# keyboard_main.net
KiCad netlist of a schematic drawn in Altium Designer
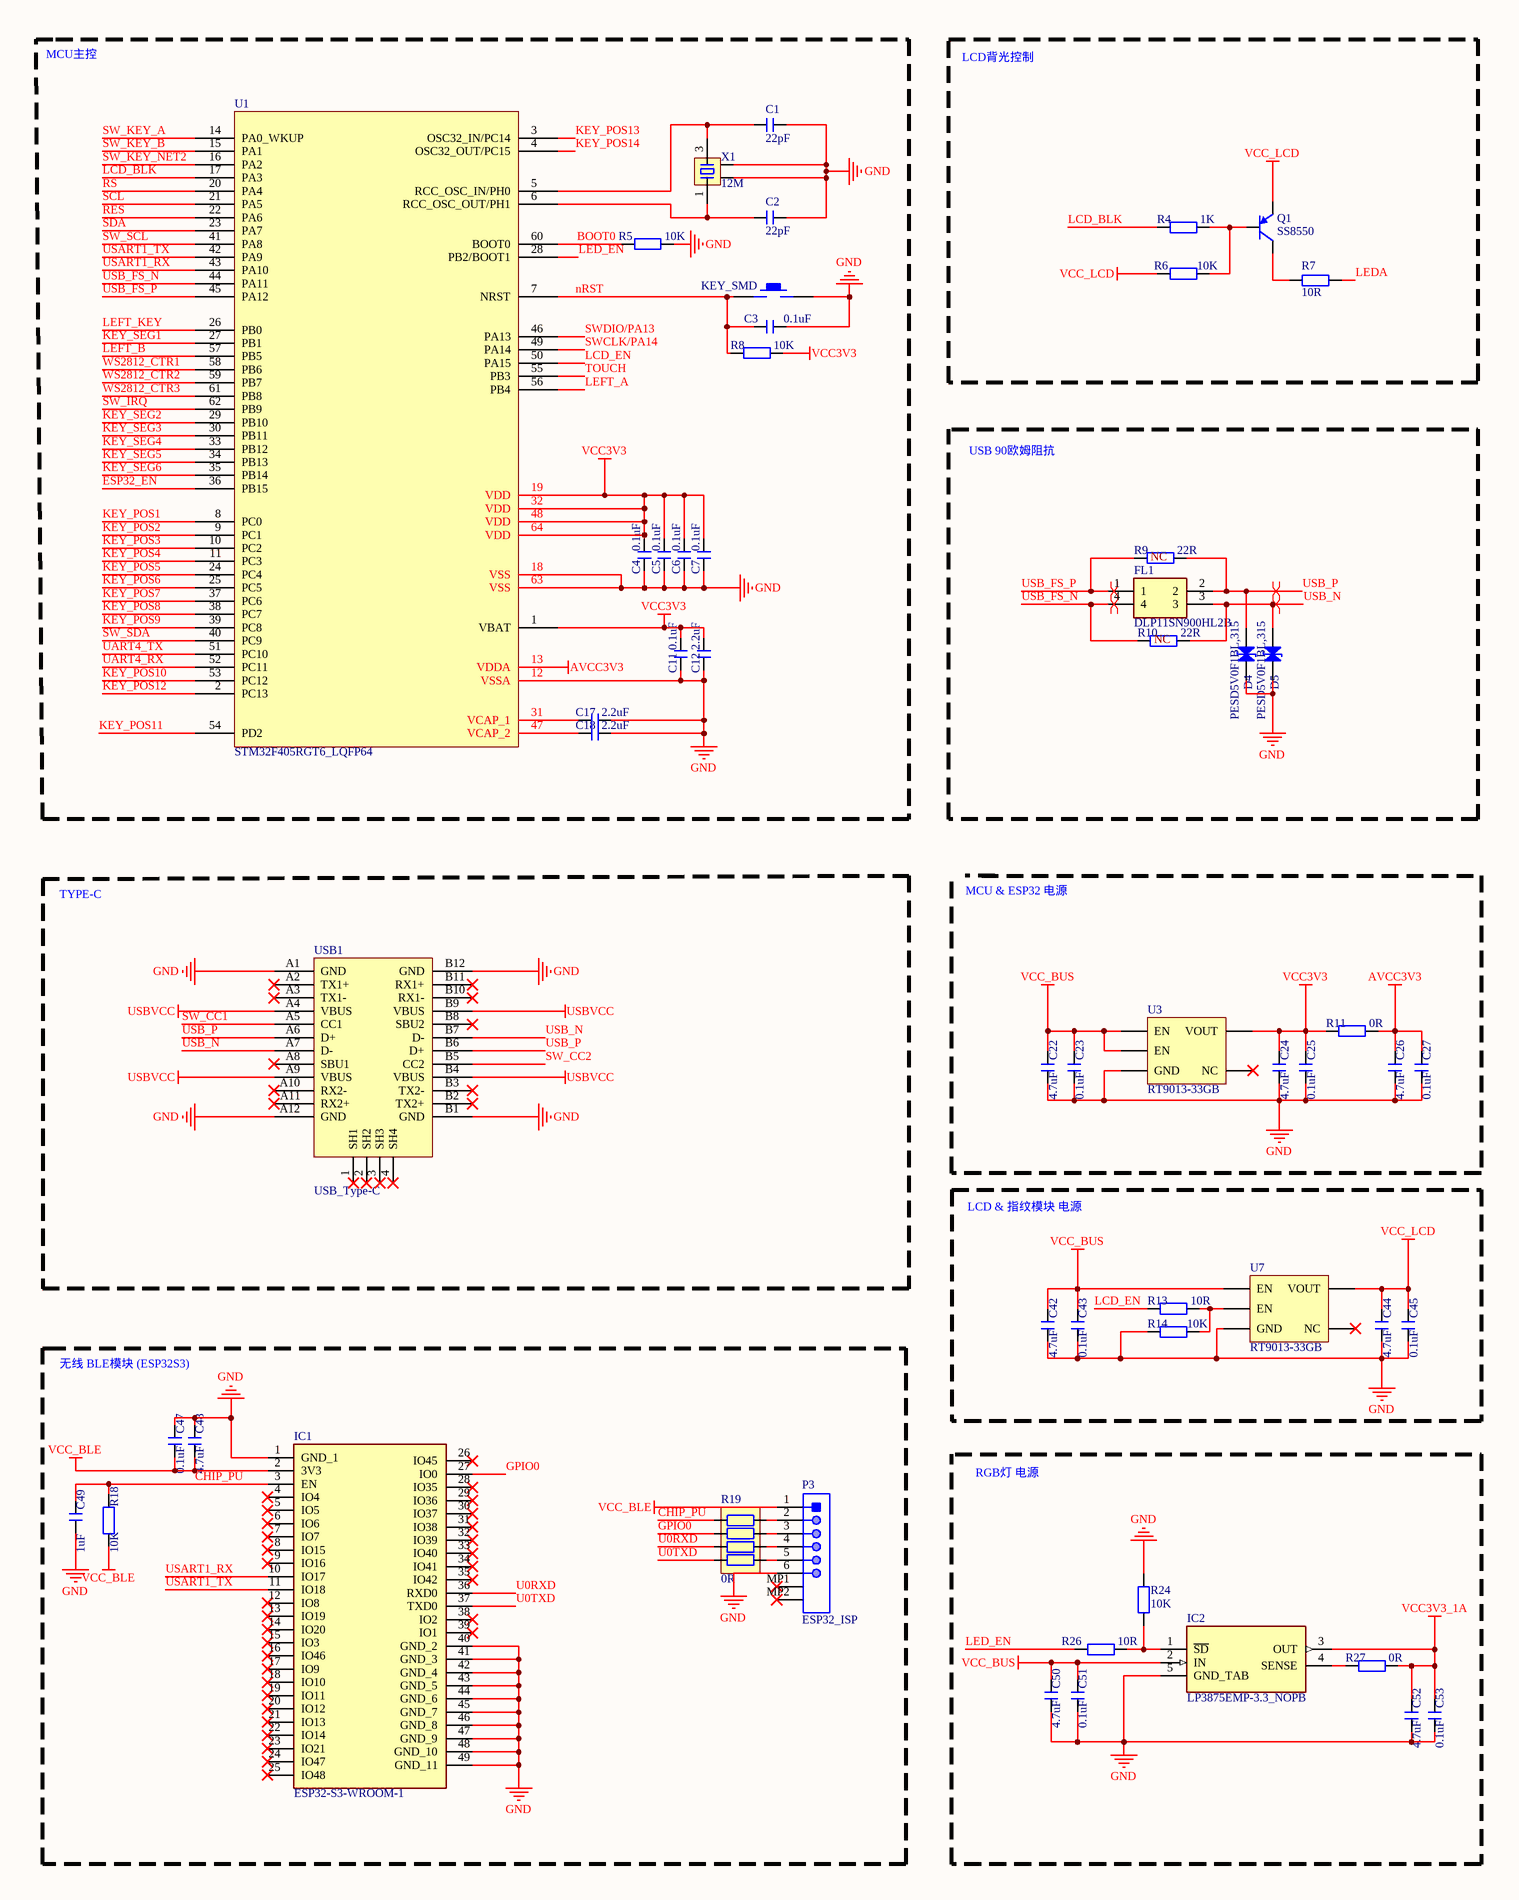
[diagram p0: keyboard_main.SchDoc, left]
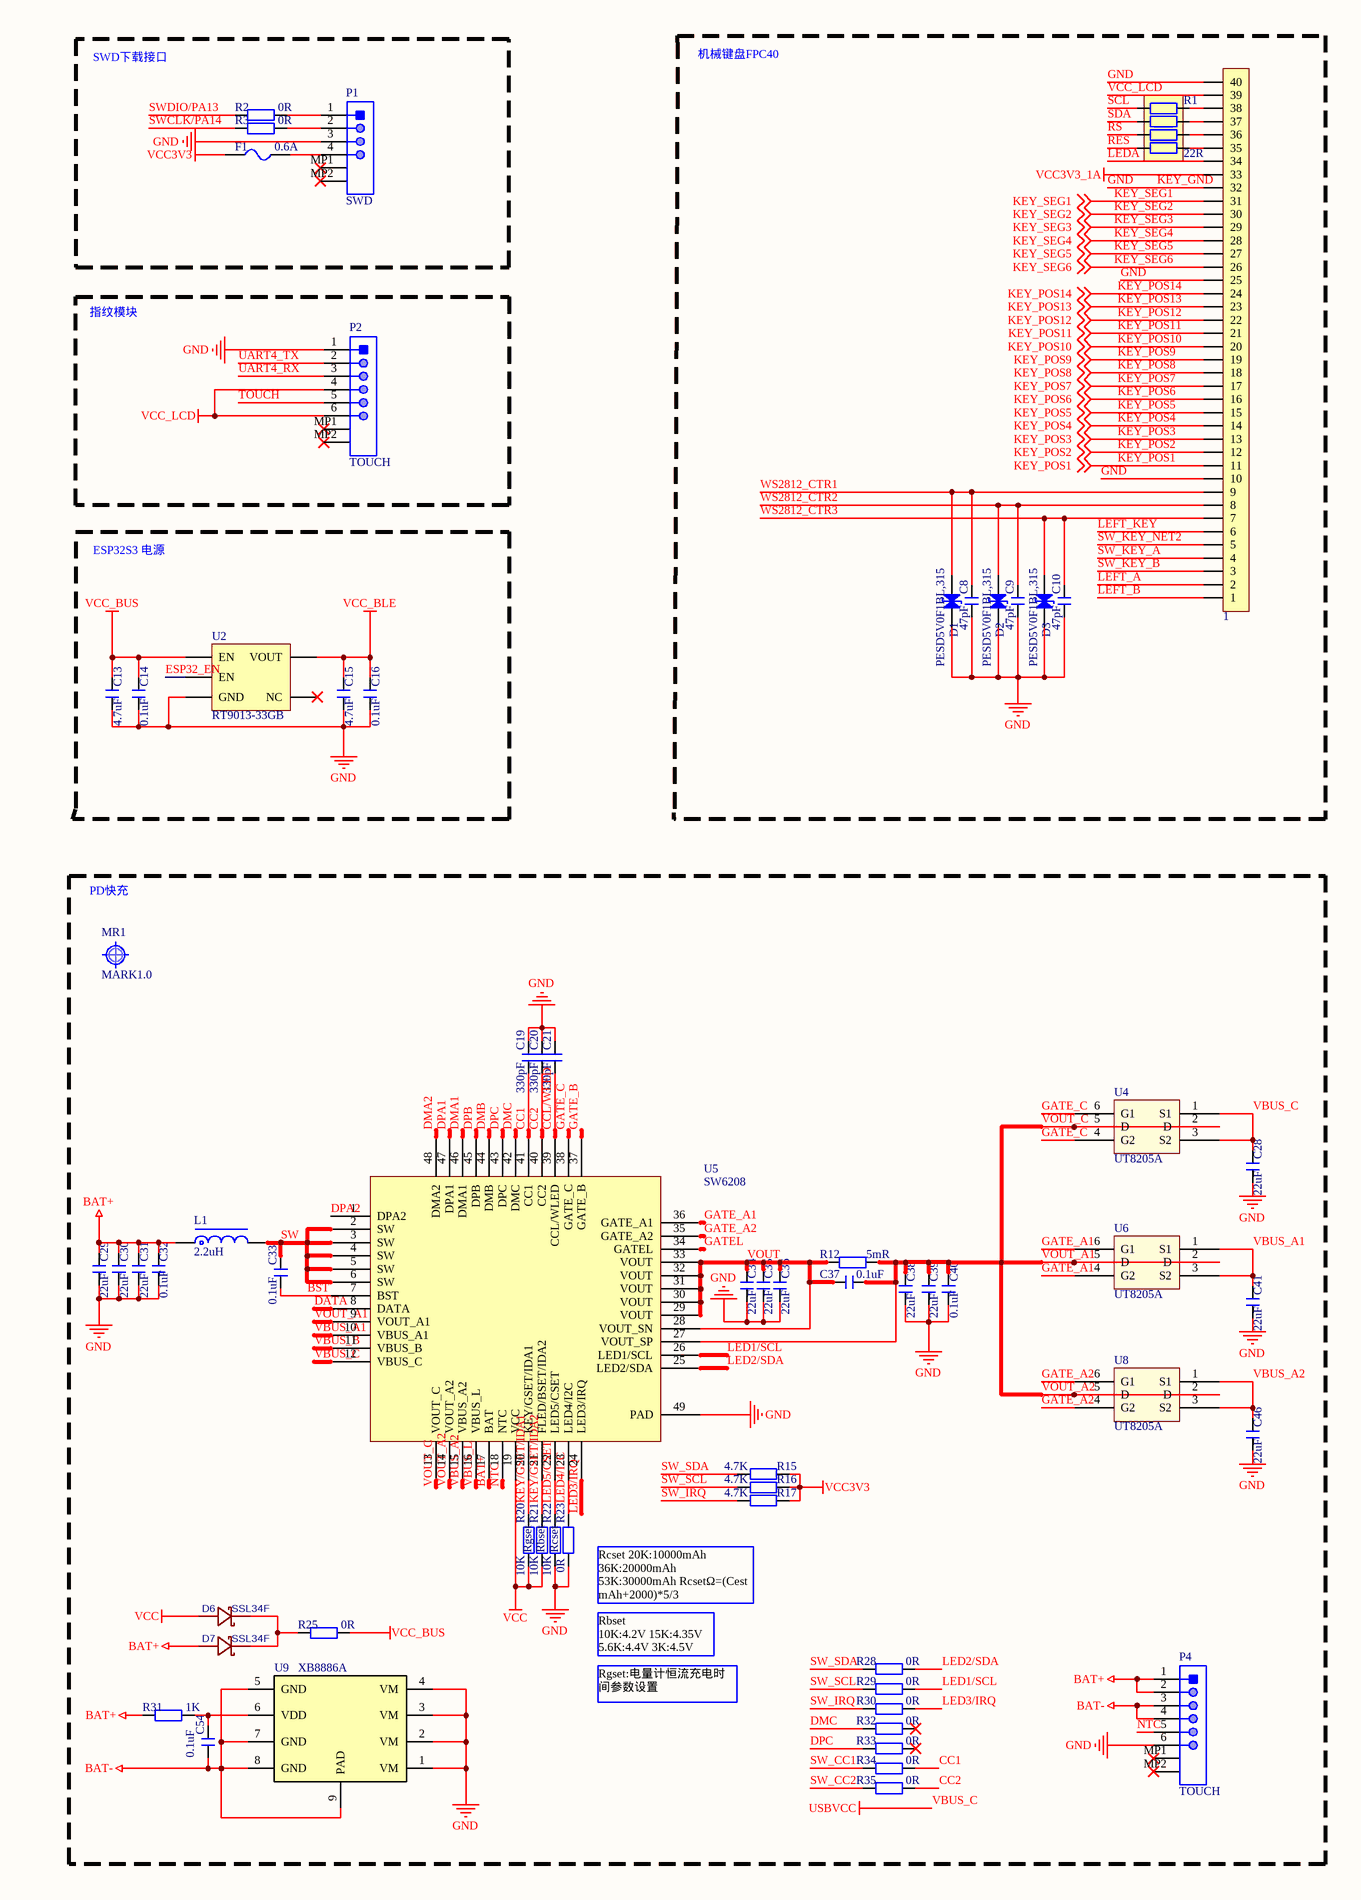
[diagram p1: keyboard_main.SchDoc, right]

(export (version "E")
  (design (tool "Eeschema 10.0.6"))
  (components
    (comp (ref "1")
      (value "FPC1.0-40P")
      (footprint "FPC0.5 2H-WS-40P")
      (description "FPC连接器")
      (fields (field (name "版权归属") "黎明电子style"))
      (libsource (lib "FPC连接器") (part "FPC-40P"))
    )
    (comp (ref "C1")
      (value "22pF")
      (footprint "C 0402_L")
      (description "贴片电容")
      (libsource (lib "0.1 - 电阻-电容-电感") (part "C"))
    )
    (comp (ref "C2")
      (value "22pF")
      (footprint "C 0402_L")
      (description "贴片电容")
      (libsource (lib "0.1 - 电阻-电容-电感") (part "C"))
    )
    (comp (ref "C3")
      (value "0.1uF")
      (footprint "C 0402_L")
      (description "贴片电容")
      (libsource (lib "0.1 - 电阻-电容-电感") (part "C"))
    )
    (comp (ref "C4")
      (value "0.1uF")
      (footprint "C 0402_L")
      (description "贴片电容")
      (libsource (lib "0.1 - 电阻-电容-电感") (part "C"))
    )
    (comp (ref "C5")
      (value "0.1uF")
      (footprint "C 0402_L")
      (description "贴片电容")
      (libsource (lib "0.1 - 电阻-电容-电感") (part "C"))
    )
    (comp (ref "C6")
      (value "0.1uF")
      (footprint "C 0402_L")
      (description "贴片电容")
      (libsource (lib "0.1 - 电阻-电容-电感") (part "C"))
    )
    (comp (ref "C7")
      (value "0.1uF")
      (footprint "C 0402_L")
      (description "贴片电容")
      (libsource (lib "0.1 - 电阻-电容-电感") (part "C"))
    )
    (comp (ref "C8")
      (value "47pF")
      (footprint "C 0402_L")
      (description "贴片电容")
      (libsource (lib "0.1 - 电阻-电容-电感") (part "C"))
    )
    (comp (ref "C9")
      (value "47pF")
      (footprint "C 0402_L")
      (description "贴片电容")
      (libsource (lib "0.1 - 电阻-电容-电感") (part "C"))
    )
    (comp (ref "C10")
      (value "47pF")
      (footprint "C 0402_L")
      (description "贴片电容")
      (libsource (lib "0.1 - 电阻-电容-电感") (part "C"))
    )
    (comp (ref "C11")
      (value "0.1uF")
      (footprint "C 0402_L")
      (description "贴片电容")
      (libsource (lib "0.1 - 电阻-电容-电感") (part "C"))
    )
    (comp (ref "C12")
      (value "2.2uF")
      (footprint "C 0402_L")
      (description "贴片电容")
      (libsource (lib "0.1 - 电阻-电容-电感") (part "C"))
    )
    (comp (ref "C13")
      (value "4.7uF")
      (footprint "C 0402_L")
      (description "贴片电容")
      (libsource (lib "0.1 - 电阻-电容-电感") (part "C"))
    )
    (comp (ref "C14")
      (value "0.1uF")
      (footprint "C 0402_L")
      (description "贴片电容")
      (libsource (lib "0.1 - 电阻-电容-电感") (part "C"))
    )
    (comp (ref "C15")
      (value "4.7uF")
      (footprint "C 0402_L")
      (description "贴片电容")
      (libsource (lib "0.1 - 电阻-电容-电感") (part "C"))
    )
    (comp (ref "C16")
      (value "0.1uF")
      (footprint "C 0402_L")
      (description "贴片电容")
      (libsource (lib "0.1 - 电阻-电容-电感") (part "C"))
    )
    (comp (ref "C17")
      (value "2.2uF")
      (footprint "C 0402_L")
      (description "贴片电容")
      (libsource (lib "0.1 - 电阻-电容-电感") (part "C"))
    )
    (comp (ref "C18")
      (value "2.2uF")
      (footprint "C 0402_L")
      (description "贴片电容")
      (libsource (lib "0.1 - 电阻-电容-电感") (part "C"))
    )
    (comp (ref "C19")
      (value "330pF")
      (footprint "C 0402_L")
      (description "贴片电容")
      (libsource (lib "0.1 - 电阻-电容-电感") (part "C"))
    )
    (comp (ref "C20")
      (value "330pF")
      (footprint "C 0402_L")
      (description "贴片电容")
      (libsource (lib "0.1 - 电阻-电容-电感") (part "C"))
    )
    (comp (ref "C21")
      (value "330pF")
      (footprint "C 0402_L")
      (description "贴片电容")
      (libsource (lib "0.1 - 电阻-电容-电感") (part "C"))
    )
    (comp (ref "C22")
      (value "4.7uF")
      (footprint "C 0402_L")
      (description "贴片电容")
      (libsource (lib "0.1 - 电阻-电容-电感") (part "C"))
    )
    (comp (ref "C23")
      (value "0.1uF")
      (footprint "C 0402_L")
      (description "贴片电容")
      (libsource (lib "0.1 - 电阻-电容-电感") (part "C"))
    )
    (comp (ref "C24")
      (value "4.7uF")
      (footprint "C 0402_L")
      (description "贴片电容")
      (libsource (lib "0.1 - 电阻-电容-电感") (part "C"))
    )
    (comp (ref "C25")
      (value "0.1uF")
      (footprint "C 0402_L")
      (description "贴片电容")
      (libsource (lib "0.1 - 电阻-电容-电感") (part "C"))
    )
    (comp (ref "C26")
      (value "4.7uF")
      (footprint "C 0402_L")
      (description "贴片电容")
      (libsource (lib "0.1 - 电阻-电容-电感") (part "C"))
    )
    (comp (ref "C27")
      (value "0.1uF")
      (footprint "C 0402_L")
      (description "贴片电容")
      (libsource (lib "0.1 - 电阻-电容-电感") (part "C"))
    )
    (comp (ref "C28")
      (value "22uF")
      (footprint "C 0805_L")
      (description "贴片电容")
      (libsource (lib "0.1 - 电阻-电容-电感") (part "C"))
    )
    (comp (ref "C29")
      (value "22uF")
      (footprint "C 0805_L")
      (description "贴片电容")
      (libsource (lib "0.1 - 电阻-电容-电感") (part "C"))
    )
    (comp (ref "C30")
      (value "22uF")
      (footprint "C 0805_L")
      (description "贴片电容")
      (libsource (lib "0.1 - 电阻-电容-电感") (part "C"))
    )
    (comp (ref "C31")
      (value "22uF")
      (footprint "C 0805_L")
      (description "贴片电容")
      (libsource (lib "0.1 - 电阻-电容-电感") (part "C"))
    )
    (comp (ref "C32")
      (value "0.1uF")
      (footprint "C 0805_L")
      (description "贴片电容")
      (libsource (lib "0.1 - 电阻-电容-电感") (part "C"))
    )
    (comp (ref "C33")
      (value "0.1uF")
      (footprint "C 0603_L")
      (description "贴片电容")
      (libsource (lib "0.1 - 电阻-电容-电感") (part "C"))
    )
    (comp (ref "C34")
      (value "22uF")
      (footprint "C 0805_L")
      (description "贴片电容")
      (libsource (lib "0.1 - 电阻-电容-电感") (part "C"))
    )
    (comp (ref "C35")
      (value "22uF")
      (footprint "C 0805_L")
      (description "贴片电容")
      (libsource (lib "0.1 - 电阻-电容-电感") (part "C"))
    )
    (comp (ref "C36")
      (value "22uF")
      (footprint "C 0805_L")
      (description "贴片电容")
      (libsource (lib "0.1 - 电阻-电容-电感") (part "C"))
    )
    (comp (ref "C37")
      (value "0.1uF")
      (footprint "C 0805_L")
      (description "贴片电容")
      (libsource (lib "0.1 - 电阻-电容-电感") (part "C"))
    )
    (comp (ref "C38")
      (value "22uF")
      (footprint "C 0805_L")
      (description "贴片电容")
      (libsource (lib "0.1 - 电阻-电容-电感") (part "C"))
    )
    (comp (ref "C39")
      (value "22uF")
      (footprint "C 0805_L")
      (description "贴片电容")
      (libsource (lib "0.1 - 电阻-电容-电感") (part "C"))
    )
    (comp (ref "C40")
      (value "0.1uF")
      (footprint "C 0805_L")
      (description "贴片电容")
      (libsource (lib "0.1 - 电阻-电容-电感") (part "C"))
    )
    (comp (ref "C41")
      (value "22uF")
      (footprint "C 0805_L")
      (description "贴片电容")
      (libsource (lib "0.1 - 电阻-电容-电感") (part "C"))
    )
    (comp (ref "C42")
      (value "4.7uF")
      (footprint "C 0402_L")
      (description "贴片电容")
      (libsource (lib "0.1 - 电阻-电容-电感") (part "C"))
    )
    (comp (ref "C43")
      (value "0.1uF")
      (footprint "C 0402_L")
      (description "贴片电容")
      (libsource (lib "0.1 - 电阻-电容-电感") (part "C"))
    )
    (comp (ref "C44")
      (value "4.7uF")
      (footprint "C 0402_L")
      (description "贴片电容")
      (libsource (lib "0.1 - 电阻-电容-电感") (part "C"))
    )
    (comp (ref "C45")
      (value "0.1uF")
      (footprint "C 0402_L")
      (description "贴片电容")
      (libsource (lib "0.1 - 电阻-电容-电感") (part "C"))
    )
    (comp (ref "C46")
      (value "22uF")
      (footprint "C 0805_L")
      (description "贴片电容")
      (libsource (lib "0.1 - 电阻-电容-电感") (part "C"))
    )
    (comp (ref "C47")
      (value "0.1uF")
      (footprint "C 0402_L")
      (description "贴片电容")
      (libsource (lib "0.1 - 电阻-电容-电感") (part "C"))
    )
    (comp (ref "C48")
      (value "4.7uF")
      (footprint "C 0402_L")
      (description "贴片电容")
      (libsource (lib "0.1 - 电阻-电容-电感") (part "C"))
    )
    (comp (ref "C49")
      (value "1uF")
      (footprint "C 0402_L")
      (description "贴片电容")
      (libsource (lib "0.1 - 电阻-电容-电感") (part "C"))
    )
    (comp (ref "C50")
      (value "4.7uF")
      (footprint "C 0402_L")
      (description "贴片电容")
      (libsource (lib "0.1 - 电阻-电容-电感") (part "C"))
    )
    (comp (ref "C51")
      (value "0.1uF")
      (footprint "C 0402_L")
      (description "贴片电容")
      (libsource (lib "0.1 - 电阻-电容-电感") (part "C"))
    )
    (comp (ref "C52")
      (value "4.7uF")
      (footprint "C 0402_L")
      (description "贴片电容")
      (libsource (lib "0.1 - 电阻-电容-电感") (part "C"))
    )
    (comp (ref "C53")
      (value "0.1uF")
      (footprint "C 0402_L")
      (description "贴片电容")
      (libsource (lib "0.1 - 电阻-电容-电感") (part "C"))
    )
    (comp (ref "C54")
      (value "0.1uF")
      (footprint "C 0805_L")
      (description "贴片电容")
      (libsource (lib "0.1 - 电阻-电容-电感") (part "C"))
    )
    (comp (ref "D1")
      (value "PESD5V0F1BL,315")
      (footprint "SOD-882_L1.0-W0.6-BI")
      (description "PESD5V0F1BL,315、ESD二极管、5.5V")
      (libsource (lib "0.2 -  二极管-整流桥") (part "PESD5V0F1BL,315"))
    )
    (comp (ref "D2")
      (value "PESD5V0F1BL,315")
      (footprint "SOD-882_L1.0-W0.6-BI")
      (description "PESD5V0F1BL,315、ESD二极管、5.5V")
      (libsource (lib "0.2 -  二极管-整流桥") (part "PESD5V0F1BL,315"))
    )
    (comp (ref "D3")
      (value "PESD5V0F1BL,315")
      (footprint "SOD-882_L1.0-W0.6-BI")
      (description "PESD5V0F1BL,315、ESD二极管、5.5V")
      (libsource (lib "0.2 -  二极管-整流桥") (part "PESD5V0F1BL,315"))
    )
    (comp (ref "D4")
      (value "PESD5V0F1BL,315")
      (footprint "SOD-882_L1.0-W0.6-BI")
      (description "PESD5V0F1BL,315、ESD二极管、5.5V")
      (libsource (lib "0.2 -  二极管-整流桥") (part "PESD5V0F1BL,315"))
    )
    (comp (ref "D5")
      (value "PESD5V0F1BL,315")
      (footprint "SOD-882_L1.0-W0.6-BI")
      (description "PESD5V0F1BL,315、ESD二极管、5.5V")
      (libsource (lib "0.2 -  二极管-整流桥") (part "PESD5V0F1BL,315"))
    )
    (comp (ref "D6")
      (value "SSL34F")
      (footprint "SMAF_L3.5-W2.6-LS4.7-RD")
      (fields (field (name "BOM_SUPPLIER PART") "C1884559") (field (name "CONTRIBUTOR") "LCSC"))
      (libsource (lib "mx_pcb_library") (part "SSL34F_C1884559"))
    )
    (comp (ref "D7")
      (value "SSL34F")
      (footprint "SMAF_L3.5-W2.6-LS4.7-RD")
      (fields (field (name "BOM_SUPPLIER PART") "C1884559") (field (name "CONTRIBUTOR") "LCSC"))
      (libsource (lib "mx_pcb_library") (part "SSL34F_C1884559"))
    )
    (comp (ref "F1")
      (value "0.6A")
      (footprint "FU 0402")
      (description "贴片保险丝")
      (libsource (lib "2.0 - 保险丝-晶振-光耦") (part "FU"))
    )
    (comp (ref "FL1")
      (value "DLP11SN900HL2B")
      (footprint "vSeasky:DLP11SA350HL2B")
      (description "Filter")
      (fields (field (name "MOUSER PART NUMBER") "81-DLP11SN900HL2B"))
      (libsource (lib "vSeasky") (part "DLP11SN900HL2B"))
    )
    (comp (ref "IC1")
      (value "ESP32-S3-WROOM-1")
      (footprint "mx_pcb_library:ESP32S3WROOM1")
      (description "Integrated Circuit")
      (libsource (lib "mx_pcb_library") (part "ESP32-S3-WROOM-1"))
    )
    (comp (ref "IC2")
      (value "LP3875EMP-3.3_NOPB")
      (footprint "mx_pcb_library:SOT150P700X180-5N")
      (description "Integrated Circuit")
      (fields
        (field (name "MANUFACTURER_PART_NUMBER") "LP3875EMP-3.3/NOPB")
        (field (name "MOUSER PART NUMBER") "926-LP3875EMP33NOPB")
      )
      (libsource (lib "mx_pcb_library") (part "LP3875EMP-3.3_NOPB"))
    )
    (comp (ref "KEY1")
      (value "KEY_SMD")
      (footprint "SMD-3.2*4.2")
      (libsource (lib "mx_pcb_library") (part "KEY_SMD"))
    )
    (comp (ref "L1")
      (value "2.2uH")
      (footprint "CD32")
      (description "CD系列贴片线绕功率电感")
      (libsource (lib "0.1 - 电阻-电容-电感") (part "L-SMD"))
    )
    (comp (ref "MR1")
      (value "MARK1.0")
      (footprint "Mark 1")
      (description "光学定位点")
      (libsource (lib "4.1 - 未分类器件") (part "MARK"))
    )
    (comp (ref "P1")
      (value "SWD")
      (footprint "JST-SM04B-SRSS-TB_V")
      (description "Male Header, Pitch 1 mm, 1 x 4 Position, Height 2.9 mm, -25 to 85 degC, RoHS, Tape and Reel")
      (fields (field (name "MANUFACTURER") "JST"))
      (libsource (lib "JST SH Connector") (part "SM04B-SRSS-TB(LF)(SN)"))
    )
    (comp (ref "P2")
      (value "TOUCH")
      (footprint "JST-SM06B-SRSS-TB_V")
      (description "Male Header, Pitch 1 mm, 1 x 6 Position, Height 2.9 mm, -25 to 85 degC, RoHS, Tape and Reel")
      (fields (field (name "MANUFACTURER") "JST"))
      (libsource (lib "JST SH Connector") (part "SM06B-SRSS-TB(LF)(SN)"))
    )
    (comp (ref "P3")
      (value "ESP32_ISP")
      (footprint "JST-SM06B-SRSS-TB_V")
      (description "Male Header, Pitch 1 mm, 1 x 6 Position, Height 2.9 mm, -25 to 85 degC, RoHS, Tape and Reel")
      (fields (field (name "MANUFACTURER") "JST"))
      (libsource (lib "JST SH Connector") (part "SM06B-SRSS-TB(LF)(SN)"))
    )
    (comp (ref "P4")
      (value "TOUCH")
      (footprint "JST-SM06B-SRSS-TB_V")
      (description "Male Header, Pitch 1 mm, 1 x 6 Position, Height 2.9 mm, -25 to 85 degC, RoHS, Tape and Reel")
      (fields (field (name "MANUFACTURER") "JST"))
      (libsource (lib "JST SH Connector") (part "SM06B-SRSS-TB(LF)(SN)"))
    )
    (comp (ref "Q1")
      (value "SS8550")
      (footprint "SOT23-3N")
      (description "高频放大-PNP型")
      (libsource (lib "0.4 - 三极管") (part "8550-SMD"))
    )
    (comp (ref "R1")
      (value "22R")
      (footprint "RCA-8P4R-0402")
      (description "贴片排阻")
      (libsource (lib "") (part "R-8P4R_1"))
    )
    (comp (ref "R2")
      (value "0R")
      (footprint "R 0402_L")
      (description "贴片电阻")
      (libsource (lib "0.1 - 电阻-电容-电感") (part "R"))
    )
    (comp (ref "R3")
      (value "0R")
      (footprint "R 0402_L")
      (description "贴片电阻")
      (libsource (lib "0.1 - 电阻-电容-电感") (part "R"))
    )
    (comp (ref "R4")
      (value "1K")
      (footprint "R 0402_L")
      (description "贴片电阻")
      (libsource (lib "0.1 - 电阻-电容-电感") (part "R"))
    )
    (comp (ref "R5")
      (value "10K")
      (footprint "R 0402_L")
      (description "贴片电阻")
      (libsource (lib "0.1 - 电阻-电容-电感") (part "R"))
    )
    (comp (ref "R6")
      (value "10K")
      (footprint "R 0402_L")
      (description "贴片电阻")
      (libsource (lib "0.1 - 电阻-电容-电感") (part "R"))
    )
    (comp (ref "R7")
      (value "10R")
      (footprint "R 0402_L")
      (description "贴片电阻")
      (libsource (lib "0.1 - 电阻-电容-电感") (part "R"))
    )
    (comp (ref "R8")
      (value "10K")
      (footprint "R 0402_L")
      (description "贴片电阻")
      (libsource (lib "0.1 - 电阻-电容-电感") (part "R"))
    )
    (comp (ref "R9")
      (value "22R")
      (footprint "R 0402_L")
      (description "贴片电阻")
      (libsource (lib "0.1 - 电阻-电容-电感") (part "R"))
    )
    (comp (ref "R10")
      (value "22R")
      (footprint "R 0402_L")
      (description "贴片电阻")
      (libsource (lib "0.1 - 电阻-电容-电感") (part "R"))
    )
    (comp (ref "R11")
      (value "0R")
      (footprint "R 0402_L")
      (description "贴片电阻")
      (libsource (lib "0.1 - 电阻-电容-电感") (part "R"))
    )
    (comp (ref "R12")
      (value "5mR")
      (footprint "R 1206_L")
      (description "贴片电阻")
      (libsource (lib "0.1 - 电阻-电容-电感") (part "R"))
    )
    (comp (ref "R13")
      (value "10R")
      (footprint "R 0402_L")
      (description "贴片电阻")
      (libsource (lib "0.1 - 电阻-电容-电感") (part "R"))
    )
    (comp (ref "R14")
      (value "10K")
      (footprint "R 0402_L")
      (description "贴片电阻")
      (libsource (lib "0.1 - 电阻-电容-电感") (part "R"))
    )
    (comp (ref "R15")
      (value "4.7K")
      (footprint "R 0402_L")
      (description "贴片电阻")
      (libsource (lib "0.1 - 电阻-电容-电感") (part "R"))
    )
    (comp (ref "R16")
      (value "4.7K")
      (footprint "R 0402_L")
      (description "贴片电阻")
      (libsource (lib "0.1 - 电阻-电容-电感") (part "R"))
    )
    (comp (ref "R17")
      (value "4.7K")
      (footprint "R 0402_L")
      (description "贴片电阻")
      (libsource (lib "0.1 - 电阻-电容-电感") (part "R"))
    )
    (comp (ref "R18")
      (value "10K")
      (footprint "R 0402_L")
      (description "贴片电阻")
      (libsource (lib "0.1 - 电阻-电容-电感") (part "R"))
    )
    (comp (ref "R19")
      (value "0R")
      (footprint "RCA-8P4R-0402")
      (description "贴片排阻")
      (libsource (lib "0.1 - 电阻-电容-电感") (part "R-8P4R"))
    )
    (comp (ref "R20")
      (value "10K")
      (footprint "R 0402_L")
      (description "贴片电阻")
      (libsource (lib "0.1 - 电阻-电容-电感") (part "R"))
    )
    (comp (ref "R21")
      (value "10K")
      (footprint "R 0402_L")
      (description "贴片电阻")
      (libsource (lib "0.1 - 电阻-电容-电感") (part "R"))
    )
    (comp (ref "R22")
      (value "10K")
      (footprint "R 0402_L")
      (description "贴片电阻")
      (libsource (lib "0.1 - 电阻-电容-电感") (part "R"))
    )
    (comp (ref "R23")
      (value "0R")
      (footprint "R 0402_L")
      (description "贴片电阻")
      (libsource (lib "0.1 - 电阻-电容-电感") (part "R"))
    )
    (comp (ref "R24")
      (value "10K")
      (footprint "R 0402_L")
      (description "贴片电阻")
      (libsource (lib "0.1 - 电阻-电容-电感") (part "R"))
    )
    (comp (ref "R25")
      (value "0R")
      (footprint "R 0402_L")
      (description "贴片电阻")
      (libsource (lib "0.1 - 电阻-电容-电感") (part "R"))
    )
    (comp (ref "R26")
      (value "10R")
      (footprint "R 0402_L")
      (description "贴片电阻")
      (libsource (lib "0.1 - 电阻-电容-电感") (part "R"))
    )
    (comp (ref "R27")
      (value "0R")
      (footprint "R 0402_L")
      (description "贴片电阻")
      (libsource (lib "0.1 - 电阻-电容-电感") (part "R"))
    )
    (comp (ref "R28")
      (value "0R")
      (footprint "R 0402_L")
      (description "贴片电阻")
      (libsource (lib "0.1 - 电阻-电容-电感") (part "R"))
    )
    (comp (ref "R29")
      (value "0R")
      (footprint "R 0402_L")
      (description "贴片电阻")
      (libsource (lib "0.1 - 电阻-电容-电感") (part "R"))
    )
    (comp (ref "R30")
      (value "0R")
      (footprint "R 0402_L")
      (description "贴片电阻")
      (libsource (lib "0.1 - 电阻-电容-电感") (part "R"))
    )
    (comp (ref "R31")
      (value "1K")
      (footprint "R 0402_L")
      (description "贴片电阻")
      (libsource (lib "0.1 - 电阻-电容-电感") (part "R"))
    )
    (comp (ref "R32")
      (value "0R")
      (footprint "R 0402_L")
      (description "贴片电阻")
      (libsource (lib "0.1 - 电阻-电容-电感") (part "R"))
    )
    (comp (ref "R33")
      (value "0R")
      (footprint "R 0402_L")
      (description "贴片电阻")
      (libsource (lib "0.1 - 电阻-电容-电感") (part "R"))
    )
    (comp (ref "R34")
      (value "0R")
      (footprint "R 0402_L")
      (description "贴片电阻")
      (libsource (lib "0.1 - 电阻-电容-电感") (part "R"))
    )
    (comp (ref "R35")
      (value "0R")
      (footprint "R 0402_L")
      (description "贴片电阻")
      (libsource (lib "0.1 - 电阻-电容-电感") (part "R"))
    )
    (comp (ref "U1")
      (value "STM32F405RGT6_LQFP64")
      (footprint "LQFP-64_10X10X05P")
      (libsource (lib "mx_pcb_library") (part "STM32F405RGT6_LQFP64"))
    )
    (comp (ref "U2")
      (value "RT9013-33GB")
      (footprint "SOT23-5M")
      (libsource (lib "mx_pcb_library") (part "RT9013-33GB"))
    )
    (comp (ref "U3")
      (value "RT9013-33GB")
      (footprint "SOT23-5M")
      (libsource (lib "mx_pcb_library") (part "RT9013-33GB"))
    )
    (comp (ref "U4")
      (value "UT8205A")
      (footprint "mx_pcb_library:SOT23-6")
      (libsource (lib "mx_pcb_library") (part "UT8205A"))
    )
    (comp (ref "U5")
      (value "SW6208")
      (footprint "QFN-48_6x6")
      (description "充电宝芯片")
      (libsource (lib "mx_pcb_library") (part "SW6208"))
    )
    (comp (ref "U6")
      (value "UT8205A")
      (footprint "mx_pcb_library:SOT23-6")
      (libsource (lib "mx_pcb_library") (part "UT8205A"))
    )
    (comp (ref "U7")
      (value "RT9013-33GB")
      (footprint "SOT23-5M")
      (libsource (lib "mx_pcb_library") (part "RT9013-33GB"))
    )
    (comp (ref "U8")
      (value "UT8205A")
      (footprint "mx_pcb_library:SOT23-6")
      (libsource (lib "mx_pcb_library") (part "UT8205A"))
    )
    (comp (ref "U9")
      (value "XB8886A")
      (footprint "mx_pcb_library:SO-8-PAD")
      (fields (field (name "MF") "Texas Instruments") (field (name "MP") "NE5532D"))
      (libsource (lib "mx_pcb_library") (part "XB8886A"))
    )
    (comp (ref "USB1")
      (value "USB_Type-C")
      (footprint "Type-C-TOP")
      (libsource (lib "mx_pcb_library") (part "USB_Type-C"))
    )
    (comp (ref "X1")
      (value "12M")
      (footprint "OSC 3225-4P")
      (description "4脚无源晶振")
      (libsource (lib "2.0 - 保险丝-晶振-光耦") (part "XTAL-4P"))
    )
  )
  (nets
    (net (code "1") (name "/BOOT0") (class "Default")
      (node (ref "R5") (pin "1") (pinfunction "1_1") (pintype "passive"))
      (node (ref "U1") (pin "60") (pinfunction "BOOT0_60") (pintype "passive"))
    )
    (net (code "2") (name "/BST") (class "Default")
      (node (ref "C33") (pin "1") (pinfunction "1_1") (pintype "passive"))
      (node (ref "U5") (pin "7") (pinfunction "BST_7") (pintype "passive"))
    )
    (net (code "3") (name "/CC1") (class "Default")
      (node (ref "C19") (pin "1") (pinfunction "1_1") (pintype "passive"))
      (node (ref "R34") (pin "2") (pinfunction "2_2") (pintype "passive"))
      (node (ref "U5") (pin "41") (pinfunction "CC1_41") (pintype "passive"))
    )
    (net (code "4") (name "/CC2") (class "Default")
      (node (ref "C20") (pin "1") (pinfunction "1_1") (pintype "passive"))
      (node (ref "R35") (pin "2") (pinfunction "2_2") (pintype "passive"))
      (node (ref "U5") (pin "40") (pinfunction "CC2_40") (pintype "passive"))
    )
    (net (code "5") (name "/CCL{slash}WLED") (class "Default")
      (node (ref "C21") (pin "1") (pinfunction "1_1") (pintype "passive"))
      (node (ref "U5") (pin "39") (pinfunction "CCL/WLED_39") (pintype "passive"))
    )
    (net (code "6") (name "/CHIP_PU") (class "Default")
      (node (ref "C49") (pin "1") (pinfunction "1_1") (pintype "passive"))
      (node (ref "IC1") (pin "3") (pinfunction "EN_3") (pintype "passive"))
      (node (ref "R18") (pin "1") (pinfunction "1_1") (pintype "passive"))
      (node (ref "R19") (pin "8") (pinfunction "8_8") (pintype "passive"))
    )
    (net (code "7") (name "/DATA") (class "Default")
      (node (ref "U5") (pin "8") (pinfunction "DATA_8") (pintype "passive"))
    )
    (net (code "8") (name "/DMA1") (class "Default")
      (node (ref "U5") (pin "46") (pinfunction "DMA1_46") (pintype "passive"))
    )
    (net (code "9") (name "/DMA2") (class "Default")
      (node (ref "U5") (pin "48") (pinfunction "DMA2_48") (pintype "passive"))
    )
    (net (code "10") (name "/DMB") (class "Default")
      (node (ref "U5") (pin "44") (pinfunction "DMB_44") (pintype "passive"))
    )
    (net (code "11") (name "/DMC") (class "Default")
      (node (ref "R32") (pin "1") (pinfunction "1_1") (pintype "passive"))
      (node (ref "U5") (pin "42") (pinfunction "DMC_42") (pintype "passive"))
    )
    (net (code "12") (name "/DPA1") (class "Default")
      (node (ref "U5") (pin "47") (pinfunction "DPA1_47") (pintype "passive"))
    )
    (net (code "13") (name "/DPA2") (class "Default")
      (node (ref "U5") (pin "1") (pinfunction "DPA2_1") (pintype "passive"))
    )
    (net (code "14") (name "/DPB") (class "Default")
      (node (ref "U5") (pin "45") (pinfunction "DPB_45") (pintype "passive"))
    )
    (net (code "15") (name "/DPC") (class "Default")
      (node (ref "R33") (pin "1") (pinfunction "1_1") (pintype "passive"))
      (node (ref "U5") (pin "43") (pinfunction "DPC_43") (pintype "passive"))
    )
    (net (code "16") (name "/ESP32_EN") (class "Default")
      (node (ref "U1") (pin "36") (pinfunction "PB15_36") (pintype "passive"))
      (node (ref "U2") (pin "3") (pinfunction "EN_3") (pintype "passive"))
    )
    (net (code "17") (name "/GATEL") (class "Default")
      (node (ref "U5") (pin "34") (pinfunction "GATEL_34") (pintype "passive"))
    )
    (net (code "18") (name "/GATE_A1") (class "Default")
      (node (ref "U5") (pin "36") (pinfunction "GATE_A1_36") (pintype "passive"))
      (node (ref "U6") (pin "4") (pinfunction "G2_4") (pintype "passive"))
      (node (ref "U6") (pin "6") (pinfunction "G1_6") (pintype "passive"))
    )
    (net (code "19") (name "/GATE_A2") (class "Default")
      (node (ref "U5") (pin "35") (pinfunction "GATE_A2_35") (pintype "passive"))
      (node (ref "U8") (pin "4") (pinfunction "G2_4") (pintype "passive"))
      (node (ref "U8") (pin "6") (pinfunction "G1_6") (pintype "passive"))
    )
    (net (code "20") (name "/GATE_B") (class "Default")
      (node (ref "U5") (pin "37") (pinfunction "GATE_B_37") (pintype "passive"))
    )
    (net (code "21") (name "/GATE_C") (class "Default")
      (node (ref "U4") (pin "4") (pinfunction "G2_4") (pintype "passive"))
      (node (ref "U4") (pin "6") (pinfunction "G1_6") (pintype "passive"))
      (node (ref "U5") (pin "38") (pinfunction "GATE_C_38") (pintype "passive"))
    )
    (net (code "22") (name "/GPIO0") (class "Default")
      (node (ref "IC1") (pin "27") (pinfunction "IO0_27") (pintype "passive"))
      (node (ref "R19") (pin "7") (pinfunction "7_7") (pintype "passive"))
    )
    (net (code "23") (name "/KEY{slash}GSET{slash}IDA1") (class "Default")
      (node (ref "R20") (pin "1") (pinfunction "1_1") (pintype "passive"))
      (node (ref "U5") (pin "20") (pinfunction "KEY/GSET/IDA1_20") (pintype "passive"))
    )
    (net (code "24") (name "/KEY{slash}GSET{slash}IDA2") (class "Default")
      (node (ref "R21") (pin "1") (pinfunction "1_1") (pintype "passive"))
      (node (ref "U5") (pin "21") (pinfunction "FLED/BSET/IDA2_21") (pintype "passive"))
    )
    (net (code "25") (name "/LCD_BLK") (class "Default")
      (node (ref "R4") (pin "1") (pinfunction "1_1") (pintype "passive"))
      (node (ref "U1") (pin "17") (pinfunction "PA3_17") (pintype "passive"))
    )
    (net (code "26") (name "/LCD_EN") (class "Default")
      (node (ref "R13") (pin "1") (pinfunction "1_1") (pintype "passive"))
      (node (ref "U1") (pin "50") (pinfunction "PA15_50") (pintype "passive"))
    )
    (net (code "27") (name "/LED1{slash}SCL") (class "Default")
      (node (ref "R29") (pin "2") (pinfunction "2_2") (pintype "passive"))
      (node (ref "U5") (pin "26") (pinfunction "LED1/SCL_26") (pintype "passive"))
    )
    (net (code "28") (name "/LED2{slash}SDA") (class "Default")
      (node (ref "R28") (pin "2") (pinfunction "2_2") (pintype "passive"))
      (node (ref "U5") (pin "25") (pinfunction "LED2/SDA_25") (pintype "passive"))
    )
    (net (code "29") (name "/LED3{slash}IRQ") (class "Default")
      (node (ref "R30") (pin "2") (pinfunction "2_2") (pintype "passive"))
      (node (ref "U5") (pin "24") (pinfunction "LED3/IRQ_24") (pintype "passive"))
    )
    (net (code "30") (name "/LED4{slash}I2C") (class "Default")
      (node (ref "R23") (pin "1") (pinfunction "1_1") (pintype "passive"))
      (node (ref "U5") (pin "23") (pinfunction "LED4/I2C_23") (pintype "passive"))
    )
    (net (code "31") (name "/LED5{slash}CSET") (class "Default")
      (node (ref "R22") (pin "1") (pinfunction "1_1") (pintype "passive"))
      (node (ref "U5") (pin "22") (pinfunction "LED5/CSET_22") (pintype "passive"))
    )
    (net (code "32") (name "/LEDA") (class "Default")
      (node (ref "1") (pin "34") (pinfunction "34_34") (pintype "passive"))
      (node (ref "R7") (pin "1") (pinfunction "1_1") (pintype "passive"))
    )
    (net (code "33") (name "/LED_EN") (class "Default")
      (node (ref "R26") (pin "1") (pinfunction "1_1") (pintype "passive"))
      (node (ref "U1") (pin "28") (pinfunction "PB2/BOOT1_28") (pintype "passive"))
    )
    (net (code "34") (name "/LEFT_A") (class "Default")
      (node (ref "1") (pin "2") (pinfunction "2_2") (pintype "passive"))
      (node (ref "U1") (pin "56") (pinfunction "PB4_56") (pintype "passive"))
    )
    (net (code "35") (name "/LEFT_B") (class "Default")
      (node (ref "1") (pin "1") (pinfunction "1_1") (pintype "passive"))
      (node (ref "U1") (pin "57") (pinfunction "PB5_57") (pintype "passive"))
    )
    (net (code "36") (name "/LEFT_KEY") (class "Default")
      (node (ref "1") (pin "6") (pinfunction "6_6") (pintype "passive"))
      (node (ref "U1") (pin "26") (pinfunction "PB0_26") (pintype "passive"))
    )
    (net (code "37") (name "/NTC") (class "Default")
      (node (ref "P4") (pin "5") (pinfunction "5_5") (pintype "passive"))
      (node (ref "U5") (pin "18") (pinfunction "NTC_18") (pintype "passive"))
    )
    (net (code "38") (name "/RES") (class "Default")
      (node (ref "R1") (pin "4") (pinfunction "4_4") (pintype "passive"))
      (node (ref "U1") (pin "22") (pinfunction "PA6_22") (pintype "passive"))
    )
    (net (code "39") (name "/RS") (class "Default")
      (node (ref "R1") (pin "3") (pinfunction "3_3") (pintype "passive"))
      (node (ref "U1") (pin "20") (pinfunction "PA4_20") (pintype "passive"))
    )
    (net (code "40") (name "/SCL") (class "Default")
      (node (ref "R1") (pin "1") (pinfunction "1_1") (pintype "passive"))
      (node (ref "U1") (pin "21") (pinfunction "PA5_21") (pintype "passive"))
    )
    (net (code "41") (name "/SDA") (class "Default")
      (node (ref "R1") (pin "2") (pinfunction "2_2") (pintype "passive"))
      (node (ref "U1") (pin "23") (pinfunction "PA7_23") (pintype "passive"))
    )
    (net (code "42") (name "/SW") (class "Default")
      (node (ref "C33") (pin "2") (pinfunction "2_2") (pintype "passive"))
      (node (ref "L1") (pin "2") (pinfunction "2_2") (pintype "passive"))
      (node (ref "U5") (pin "2") (pinfunction "SW_2") (pintype "passive"))
      (node (ref "U5") (pin "3") (pinfunction "SW_3") (pintype "passive"))
      (node (ref "U5") (pin "4") (pinfunction "SW_4") (pintype "passive"))
      (node (ref "U5") (pin "5") (pinfunction "SW_5") (pintype "passive"))
      (node (ref "U5") (pin "6") (pinfunction "SW_6") (pintype "passive"))
    )
    (net (code "43") (name "/SWCLK{slash}PA14") (class "Default")
      (node (ref "R3") (pin "1") (pinfunction "1_1") (pintype "passive"))
      (node (ref "U1") (pin "49") (pinfunction "PA14_49") (pintype "passive"))
    )
    (net (code "44") (name "/SWDIO{slash}PA13") (class "Default")
      (node (ref "R2") (pin "1") (pinfunction "1_1") (pintype "passive"))
      (node (ref "U1") (pin "46") (pinfunction "PA13_46") (pintype "passive"))
    )
    (net (code "45") (name "/SW_CC1") (class "Default")
      (node (ref "R34") (pin "1") (pinfunction "1_1") (pintype "passive"))
      (node (ref "USB1") (pin "A5") (pinfunction "CC1_A5") (pintype "passive"))
    )
    (net (code "46") (name "/SW_CC2") (class "Default")
      (node (ref "R35") (pin "1") (pinfunction "1_1") (pintype "passive"))
      (node (ref "USB1") (pin "B5") (pinfunction "CC2_B5") (pintype "passive"))
    )
    (net (code "47") (name "/SW_IRQ") (class "Default")
      (node (ref "R17") (pin "2") (pinfunction "2_2") (pintype "passive"))
      (node (ref "R30") (pin "1") (pinfunction "1_1") (pintype "passive"))
      (node (ref "U1") (pin "62") (pinfunction "PB9_62") (pintype "passive"))
    )
    (net (code "48") (name "/SW_KEY_A") (class "Default")
      (node (ref "1") (pin "4") (pinfunction "4_4") (pintype "passive"))
      (node (ref "U1") (pin "14") (pinfunction "PA0_WKUP_14") (pintype "passive"))
    )
    (net (code "49") (name "/SW_KEY_B") (class "Default")
      (node (ref "1") (pin "3") (pinfunction "3_3") (pintype "passive"))
      (node (ref "U1") (pin "15") (pinfunction "PA1_15") (pintype "passive"))
    )
    (net (code "50") (name "/SW_KEY_NET2") (class "Default")
      (node (ref "1") (pin "5") (pinfunction "5_5") (pintype "passive"))
      (node (ref "U1") (pin "16") (pinfunction "PA2_16") (pintype "passive"))
    )
    (net (code "51") (name "/SW_SCL") (class "Default")
      (node (ref "R16") (pin "2") (pinfunction "2_2") (pintype "passive"))
      (node (ref "R29") (pin "1") (pinfunction "1_1") (pintype "passive"))
      (node (ref "U1") (pin "41") (pinfunction "PA8_41") (pintype "passive"))
    )
    (net (code "52") (name "/SW_SDA") (class "Default")
      (node (ref "R15") (pin "2") (pinfunction "2_2") (pintype "passive"))
      (node (ref "R28") (pin "1") (pinfunction "1_1") (pintype "passive"))
      (node (ref "U1") (pin "40") (pinfunction "PC9_40") (pintype "passive"))
    )
    (net (code "53") (name "/TOUCH") (class "Default")
      (node (ref "P2") (pin "5") (pinfunction "5_5") (pintype "passive"))
      (node (ref "U1") (pin "55") (pinfunction "PB3_55") (pintype "passive"))
    )
    (net (code "54") (name "/U0RXD") (class "Default")
      (node (ref "IC1") (pin "36") (pinfunction "RXD0_36") (pintype "passive"))
      (node (ref "R19") (pin "6") (pinfunction "6_6") (pintype "passive"))
    )
    (net (code "55") (name "/U0TXD") (class "Default")
      (node (ref "IC1") (pin "37") (pinfunction "TXD0_37") (pintype "passive"))
      (node (ref "R19") (pin "5") (pinfunction "5_5") (pintype "passive"))
    )
    (net (code "56") (name "/UART4_RX") (class "Default")
      (node (ref "P2") (pin "3") (pinfunction "3_3") (pintype "passive"))
      (node (ref "U1") (pin "52") (pinfunction "PC11_52") (pintype "passive"))
    )
    (net (code "57") (name "/UART4_TX") (class "Default")
      (node (ref "P2") (pin "2") (pinfunction "2_2") (pintype "passive"))
      (node (ref "U1") (pin "51") (pinfunction "PC10_51") (pintype "passive"))
    )
    (net (code "58") (name "/USART1_RX") (class "Default")
      (node (ref "IC1") (pin "10") (pinfunction "IO17_10") (pintype "passive"))
      (node (ref "U1") (pin "43") (pinfunction "PA10_43") (pintype "passive"))
    )
    (net (code "59") (name "/USART1_TX") (class "Default")
      (node (ref "IC1") (pin "11") (pinfunction "IO18_11") (pintype "passive"))
      (node (ref "U1") (pin "42") (pinfunction "PA9_42") (pintype "passive"))
    )
    (net (code "60") (name "/USB_FS_N") (class "Default")
      (node (ref "FL1") (pin "4") (pinfunction "4_4") (pintype "passive"))
      (node (ref "R10") (pin "1") (pinfunction "1_1") (pintype "passive"))
      (node (ref "U1") (pin "44") (pinfunction "PA11_44") (pintype "passive"))
    )
    (net (code "61") (name "/USB_FS_P") (class "Default")
      (node (ref "FL1") (pin "1") (pinfunction "1_1") (pintype "passive"))
      (node (ref "R9") (pin "1") (pinfunction "1_1") (pintype "passive"))
      (node (ref "U1") (pin "45") (pinfunction "PA12_45") (pintype "passive"))
    )
    (net (code "62") (name "/USB_N") (class "Default")
      (node (ref "D5") (pin "1") (pinfunction "A_1") (pintype "passive"))
      (node (ref "FL1") (pin "3") (pinfunction "3_3") (pintype "passive"))
      (node (ref "R10") (pin "2") (pinfunction "2_2") (pintype "passive"))
      (node (ref "USB1") (pin "A7") (pinfunction "D-_A7") (pintype "passive"))
      (node (ref "USB1") (pin "B7") (pinfunction "D-_B7") (pintype "passive"))
    )
    (net (code "63") (name "/USB_P") (class "Default")
      (node (ref "D4") (pin "1") (pinfunction "A_1") (pintype "passive"))
      (node (ref "FL1") (pin "2") (pinfunction "2_2") (pintype "passive"))
      (node (ref "R9") (pin "2") (pinfunction "2_2") (pintype "passive"))
      (node (ref "USB1") (pin "A6") (pinfunction "D+_A6") (pintype "passive"))
      (node (ref "USB1") (pin "B6") (pinfunction "D+_B6") (pintype "passive"))
    )
    (net (code "64") (name "/VBUS_A1") (class "Default")
      (node (ref "C41") (pin "2") (pinfunction "2_2") (pintype "passive"))
      (node (ref "U5") (pin "10") (pinfunction "VBUS_A1_10") (pintype "passive"))
      (node (ref "U6") (pin "1") (pinfunction "S1_1") (pintype "passive"))
      (node (ref "U6") (pin "3") (pinfunction "S2_3") (pintype "passive"))
    )
    (net (code "65") (name "/VBUS_A2") (class "Default")
      (node (ref "C46") (pin "2") (pinfunction "2_2") (pintype "passive"))
      (node (ref "U5") (pin "15") (pinfunction "VBUS_A2_15") (pintype "passive"))
      (node (ref "U8") (pin "1") (pinfunction "S1_1") (pintype "passive"))
      (node (ref "U8") (pin "3") (pinfunction "S2_3") (pintype "passive"))
    )
    (net (code "66") (name "/VBUS_B") (class "Default")
      (node (ref "U5") (pin "11") (pinfunction "VBUS_B_11") (pintype "passive"))
    )
    (net (code "67") (name "/VBUS_L") (class "Default")
      (node (ref "U5") (pin "16") (pinfunction "VBUS_L_16") (pintype "passive"))
    )
    (net (code "68") (name "/VOUT") (class "Default")
      (node (ref "C34") (pin "2") (pinfunction "2_2") (pintype "passive"))
      (node (ref "C35") (pin "2") (pinfunction "2_2") (pintype "passive"))
      (node (ref "C36") (pin "2") (pinfunction "2_2") (pintype "passive"))
      (node (ref "C37") (pin "1") (pinfunction "1_1") (pintype "passive"))
      (node (ref "R12") (pin "1") (pinfunction "1_1") (pintype "passive"))
      (node (ref "U5") (pin "28") (pinfunction "VOUT_SN_28") (pintype "passive"))
      (node (ref "U5") (pin "29") (pinfunction "VOUT_29") (pintype "passive"))
      (node (ref "U5") (pin "30") (pinfunction "VOUT_30") (pintype "passive"))
      (node (ref "U5") (pin "31") (pinfunction "VOUT_31") (pintype "passive"))
      (node (ref "U5") (pin "32") (pinfunction "VOUT_32") (pintype "passive"))
      (node (ref "U5") (pin "33") (pinfunction "VOUT_33") (pintype "passive"))
    )
    (net (code "69") (name "/VOUT_A1") (class "Default")
      (node (ref "C37") (pin "2") (pinfunction "2_2") (pintype "passive"))
      (node (ref "C38") (pin "2") (pinfunction "2_2") (pintype "passive"))
      (node (ref "C39") (pin "2") (pinfunction "2_2") (pintype "passive"))
      (node (ref "C40") (pin "2") (pinfunction "2_2") (pintype "passive"))
      (node (ref "R12") (pin "2") (pinfunction "2_2") (pintype "passive"))
      (node (ref "U4") (pin "2") (pinfunction "D_2") (pintype "passive"))
      (node (ref "U4") (pin "5") (pinfunction "D_5") (pintype "passive"))
      (node (ref "U5") (pin "13") (pinfunction "VOUT_C_13") (pintype "passive"))
      (node (ref "U5") (pin "14") (pinfunction "VOUT_A2_14") (pintype "passive"))
      (node (ref "U5") (pin "27") (pinfunction "VOUT_SP_27") (pintype "passive"))
      (node (ref "U5") (pin "9") (pinfunction "VOUT_A1_9") (pintype "passive"))
      (node (ref "U6") (pin "2") (pinfunction "D_2") (pintype "passive"))
      (node (ref "U6") (pin "5") (pinfunction "D_5") (pintype "passive"))
      (node (ref "U8") (pin "2") (pinfunction "D_2") (pintype "passive"))
      (node (ref "U8") (pin "5") (pinfunction "D_5") (pintype "passive"))
    )
    (net (code "70") (name "/WS2812_CTR1") (class "Default")
      (node (ref "1") (pin "9") (pinfunction "9_9") (pintype "passive"))
      (node (ref "C8") (pin "2") (pinfunction "2_2") (pintype "passive"))
      (node (ref "D1") (pin "1") (pinfunction "A_1") (pintype "passive"))
      (node (ref "U1") (pin "58") (pinfunction "PB6_58") (pintype "passive"))
    )
    (net (code "71") (name "/WS2812_CTR2") (class "Default")
      (node (ref "1") (pin "8") (pinfunction "8_8") (pintype "passive"))
      (node (ref "C9") (pin "2") (pinfunction "2_2") (pintype "passive"))
      (node (ref "D2") (pin "1") (pinfunction "A_1") (pintype "passive"))
      (node (ref "U1") (pin "59") (pinfunction "PB7_59") (pintype "passive"))
    )
    (net (code "72") (name "/WS2812_CTR3") (class "Default")
      (node (ref "1") (pin "7") (pinfunction "7_7") (pintype "passive"))
      (node (ref "C10") (pin "2") (pinfunction "2_2") (pintype "passive"))
      (node (ref "D3") (pin "1") (pinfunction "A_1") (pintype "passive"))
      (node (ref "U1") (pin "61") (pinfunction "PB8_61") (pintype "passive"))
    )
    (net (code "73") (name "/nRST") (class "Default")
      (node (ref "C3") (pin "1") (pinfunction "1_1") (pintype "passive"))
      (node (ref "KEY1") (pin "1") (pinfunction "1_1") (pintype "passive"))
      (node (ref "R8") (pin "1") (pinfunction "1_1") (pintype "passive"))
      (node (ref "U1") (pin "7") (pinfunction "NRST_7") (pintype "passive"))
    )
    (net (code "74") (name "AVCC3V3") (class "Default")
      (node (ref "C26") (pin "1") (pinfunction "1_1") (pintype "passive"))
      (node (ref "C27") (pin "1") (pinfunction "1_1") (pintype "passive"))
      (node (ref "R11") (pin "2") (pinfunction "2_2") (pintype "passive"))
      (node (ref "U1") (pin "13") (pinfunction "VDDA_13") (pintype "passive"))
    )
    (net (code "75") (name "BAT+") (class "Default")
      (node (ref "C29") (pin "2") (pinfunction "2_2") (pintype "passive"))
      (node (ref "C30") (pin "2") (pinfunction "2_2") (pintype "passive"))
      (node (ref "C31") (pin "2") (pinfunction "2_2") (pintype "passive"))
      (node (ref "C32") (pin "2") (pinfunction "2_2") (pintype "passive"))
      (node (ref "D7") (pin "2") (pinfunction "A_2") (pintype "passive"))
      (node (ref "L1") (pin "1") (pinfunction "1_1") (pintype "passive"))
      (node (ref "P4") (pin "1") (pinfunction "1_1") (pintype "passive"))
      (node (ref "P4") (pin "2") (pinfunction "2_2") (pintype "passive"))
      (node (ref "R31") (pin "1") (pinfunction "1_1") (pintype "passive"))
      (node (ref "U5") (pin "17") (pinfunction "BAT_17") (pintype "passive"))
    )
    (net (code "76") (name "BAT-") (class "Default")
      (node (ref "C54") (pin "1") (pinfunction "1_1") (pintype "passive"))
      (node (ref "P4") (pin "3") (pinfunction "3_3") (pintype "passive"))
      (node (ref "P4") (pin "4") (pinfunction "4_4") (pintype "passive"))
      (node (ref "U9") (pin "5") (pinfunction "GND_5") (pintype "passive"))
      (node (ref "U9") (pin "7") (pinfunction "GND_7") (pintype "passive"))
      (node (ref "U9") (pin "8") (pinfunction "GND_8") (pintype "passive"))
      (node (ref "U9") (pin "9") (pinfunction "PAD_9") (pintype "passive"))
    )
    (net (code "77") (name "GND") (class "Default")
      (node (ref "1") (pin "10") (pinfunction "10_10") (pintype "passive"))
      (node (ref "1") (pin "25") (pinfunction "25_25") (pintype "passive"))
      (node (ref "1") (pin "32") (pinfunction "32_32") (pintype "passive"))
      (node (ref "1") (pin "40") (pinfunction "40_40") (pintype "passive"))
      (node (ref "C1") (pin "2") (pinfunction "2_2") (pintype "passive"))
      (node (ref "C10") (pin "1") (pinfunction "1_1") (pintype "passive"))
      (node (ref "C11") (pin "1") (pinfunction "1_1") (pintype "passive"))
      (node (ref "C12") (pin "1") (pinfunction "1_1") (pintype "passive"))
      (node (ref "C13") (pin "2") (pinfunction "2_2") (pintype "passive"))
      (node (ref "C14") (pin "2") (pinfunction "2_2") (pintype "passive"))
      (node (ref "C15") (pin "2") (pinfunction "2_2") (pintype "passive"))
      (node (ref "C16") (pin "2") (pinfunction "2_2") (pintype "passive"))
      (node (ref "C17") (pin "1") (pinfunction "1_1") (pintype "passive"))
      (node (ref "C18") (pin "1") (pinfunction "1_1") (pintype "passive"))
      (node (ref "C19") (pin "2") (pinfunction "2_2") (pintype "passive"))
      (node (ref "C2") (pin "2") (pinfunction "2_2") (pintype "passive"))
      (node (ref "C20") (pin "2") (pinfunction "2_2") (pintype "passive"))
      (node (ref "C21") (pin "2") (pinfunction "2_2") (pintype "passive"))
      (node (ref "C22") (pin "2") (pinfunction "2_2") (pintype "passive"))
      (node (ref "C23") (pin "2") (pinfunction "2_2") (pintype "passive"))
      (node (ref "C24") (pin "2") (pinfunction "2_2") (pintype "passive"))
      (node (ref "C25") (pin "2") (pinfunction "2_2") (pintype "passive"))
      (node (ref "C26") (pin "2") (pinfunction "2_2") (pintype "passive"))
      (node (ref "C27") (pin "2") (pinfunction "2_2") (pintype "passive"))
      (node (ref "C28") (pin "1") (pinfunction "1_1") (pintype "passive"))
      (node (ref "C29") (pin "1") (pinfunction "1_1") (pintype "passive"))
      (node (ref "C3") (pin "2") (pinfunction "2_2") (pintype "passive"))
      (node (ref "C30") (pin "1") (pinfunction "1_1") (pintype "passive"))
      (node (ref "C31") (pin "1") (pinfunction "1_1") (pintype "passive"))
      (node (ref "C32") (pin "1") (pinfunction "1_1") (pintype "passive"))
      (node (ref "C34") (pin "1") (pinfunction "1_1") (pintype "passive"))
      (node (ref "C35") (pin "1") (pinfunction "1_1") (pintype "passive"))
      (node (ref "C36") (pin "1") (pinfunction "1_1") (pintype "passive"))
      (node (ref "C38") (pin "1") (pinfunction "1_1") (pintype "passive"))
      (node (ref "C39") (pin "1") (pinfunction "1_1") (pintype "passive"))
      (node (ref "C4") (pin "1") (pinfunction "1_1") (pintype "passive"))
      (node (ref "C40") (pin "1") (pinfunction "1_1") (pintype "passive"))
      (node (ref "C41") (pin "1") (pinfunction "1_1") (pintype "passive"))
      (node (ref "C42") (pin "2") (pinfunction "2_2") (pintype "passive"))
      (node (ref "C43") (pin "2") (pinfunction "2_2") (pintype "passive"))
      (node (ref "C44") (pin "2") (pinfunction "2_2") (pintype "passive"))
      (node (ref "C45") (pin "2") (pinfunction "2_2") (pintype "passive"))
      (node (ref "C46") (pin "1") (pinfunction "1_1") (pintype "passive"))
      (node (ref "C47") (pin "1") (pinfunction "1_1") (pintype "passive"))
      (node (ref "C48") (pin "1") (pinfunction "1_1") (pintype "passive"))
      (node (ref "C49") (pin "2") (pinfunction "2_2") (pintype "passive"))
      (node (ref "C5") (pin "1") (pinfunction "1_1") (pintype "passive"))
      (node (ref "C50") (pin "2") (pinfunction "2_2") (pintype "passive"))
      (node (ref "C51") (pin "2") (pinfunction "2_2") (pintype "passive"))
      (node (ref "C52") (pin "2") (pinfunction "2_2") (pintype "passive"))
      (node (ref "C53") (pin "2") (pinfunction "2_2") (pintype "passive"))
      (node (ref "C6") (pin "1") (pinfunction "1_1") (pintype "passive"))
      (node (ref "C7") (pin "1") (pinfunction "1_1") (pintype "passive"))
      (node (ref "C8") (pin "1") (pinfunction "1_1") (pintype "passive"))
      (node (ref "C9") (pin "1") (pinfunction "1_1") (pintype "passive"))
      (node (ref "D1") (pin "2") (pinfunction "K_2") (pintype "passive"))
      (node (ref "D2") (pin "2") (pinfunction "K_2") (pintype "passive"))
      (node (ref "D3") (pin "2") (pinfunction "K_2") (pintype "passive"))
      (node (ref "D4") (pin "2") (pinfunction "K_2") (pintype "passive"))
      (node (ref "D5") (pin "2") (pinfunction "K_2") (pintype "passive"))
      (node (ref "IC1") (pin "1") (pinfunction "GND_1_1") (pintype "passive"))
      (node (ref "IC1") (pin "40") (pinfunction "GND_2_40") (pintype "passive"))
      (node (ref "IC1") (pin "41") (pinfunction "GND_3_41") (pintype "passive"))
      (node (ref "IC1") (pin "42") (pinfunction "GND_4_42") (pintype "passive"))
      (node (ref "IC1") (pin "43") (pinfunction "GND_5_43") (pintype "passive"))
      (node (ref "IC1") (pin "44") (pinfunction "GND_6_44") (pintype "passive"))
      (node (ref "IC1") (pin "45") (pinfunction "GND_7_45") (pintype "passive"))
      (node (ref "IC1") (pin "46") (pinfunction "GND_8_46") (pintype "passive"))
      (node (ref "IC1") (pin "47") (pinfunction "GND_9_47") (pintype "passive"))
      (node (ref "IC1") (pin "48") (pinfunction "GND_10_48") (pintype "passive"))
      (node (ref "IC1") (pin "49") (pinfunction "GND_11_49") (pintype "passive"))
      (node (ref "IC2") (pin "5") (pinfunction "GND_TAB_5") (pintype "power_in"))
      (node (ref "KEY1") (pin "2") (pinfunction "2_2") (pintype "passive"))
      (node (ref "P1") (pin "3") (pinfunction "3_3") (pintype "passive"))
      (node (ref "P2") (pin "1") (pinfunction "1_1") (pintype "passive"))
      (node (ref "P3") (pin "6") (pinfunction "6_6") (pintype "passive"))
      (node (ref "P4") (pin "6") (pinfunction "6_6") (pintype "passive"))
      (node (ref "R14") (pin "2") (pinfunction "2_2") (pintype "passive"))
      (node (ref "R22") (pin "2") (pinfunction "2_2") (pintype "passive"))
      (node (ref "R23") (pin "2") (pinfunction "2_2") (pintype "passive"))
      (node (ref "R24") (pin "1") (pinfunction "1_1") (pintype "passive"))
      (node (ref "R5") (pin "2") (pinfunction "2_2") (pintype "passive"))
      (node (ref "U1") (pin "12") (pinfunction "VSSA_12") (pintype "passive"))
      (node (ref "U1") (pin "18") (pinfunction "VSS_18") (pintype "passive"))
      (node (ref "U1") (pin "63") (pinfunction "VSS_63") (pintype "passive"))
      (node (ref "U2") (pin "2") (pinfunction "GND_2") (pintype "passive"))
      (node (ref "U3") (pin "2") (pinfunction "GND_2") (pintype "passive"))
      (node (ref "U5") (pin "49") (pinfunction "PAD_49") (pintype "passive"))
      (node (ref "U7") (pin "2") (pinfunction "GND_2") (pintype "passive"))
      (node (ref "U9") (pin "1") (pinfunction "VM_1") (pintype "passive"))
      (node (ref "U9") (pin "2") (pinfunction "VM_2") (pintype "passive"))
      (node (ref "U9") (pin "3") (pinfunction "VM_3") (pintype "passive"))
      (node (ref "U9") (pin "4") (pinfunction "VM_4") (pintype "passive"))
      (node (ref "USB1") (pin "A1") (pinfunction "GND_A1") (pintype "passive"))
      (node (ref "USB1") (pin "A12") (pinfunction "GND_A12") (pintype "passive"))
      (node (ref "USB1") (pin "B1") (pinfunction "GND_B1") (pintype "passive"))
      (node (ref "USB1") (pin "B12") (pinfunction "GND_B12") (pintype "passive"))
      (node (ref "X1") (pin "2") (pinfunction "2_2") (pintype "passive"))
      (node (ref "X1") (pin "4") (pinfunction "4_4") (pintype "passive"))
    )
    (net (code "78") (name "KEY_POS1") (class "Default")
      (node (ref "1") (pin "11") (pinfunction "11_11") (pintype "passive"))
      (node (ref "U1") (pin "8") (pinfunction "PC0_8") (pintype "passive"))
    )
    (net (code "79") (name "KEY_POS2") (class "Default")
      (node (ref "1") (pin "12") (pinfunction "12_12") (pintype "passive"))
      (node (ref "U1") (pin "9") (pinfunction "PC1_9") (pintype "passive"))
    )
    (net (code "80") (name "KEY_POS3") (class "Default")
      (node (ref "1") (pin "13") (pinfunction "13_13") (pintype "passive"))
      (node (ref "U1") (pin "10") (pinfunction "PC2_10") (pintype "passive"))
    )
    (net (code "81") (name "KEY_POS4") (class "Default")
      (node (ref "1") (pin "14") (pinfunction "14_14") (pintype "passive"))
      (node (ref "U1") (pin "11") (pinfunction "PC3_11") (pintype "passive"))
    )
    (net (code "82") (name "KEY_POS5") (class "Default")
      (node (ref "1") (pin "15") (pinfunction "15_15") (pintype "passive"))
      (node (ref "U1") (pin "24") (pinfunction "PC4_24") (pintype "passive"))
    )
    (net (code "83") (name "KEY_POS6") (class "Default")
      (node (ref "1") (pin "16") (pinfunction "16_16") (pintype "passive"))
      (node (ref "U1") (pin "25") (pinfunction "PC5_25") (pintype "passive"))
    )
    (net (code "84") (name "KEY_POS7") (class "Default")
      (node (ref "1") (pin "17") (pinfunction "17_17") (pintype "passive"))
      (node (ref "U1") (pin "37") (pinfunction "PC6_37") (pintype "passive"))
    )
    (net (code "85") (name "KEY_POS8") (class "Default")
      (node (ref "1") (pin "18") (pinfunction "18_18") (pintype "passive"))
      (node (ref "U1") (pin "38") (pinfunction "PC7_38") (pintype "passive"))
    )
    (net (code "86") (name "KEY_POS9") (class "Default")
      (node (ref "1") (pin "19") (pinfunction "19_19") (pintype "passive"))
      (node (ref "U1") (pin "39") (pinfunction "PC8_39") (pintype "passive"))
    )
    (net (code "87") (name "KEY_POS10") (class "Default")
      (node (ref "1") (pin "20") (pinfunction "20_20") (pintype "passive"))
      (node (ref "U1") (pin "53") (pinfunction "PC12_53") (pintype "passive"))
    )
    (net (code "88") (name "KEY_POS11") (class "Default")
      (node (ref "1") (pin "21") (pinfunction "21_21") (pintype "passive"))
      (node (ref "U1") (pin "54") (pinfunction "PD2_54") (pintype "passive"))
    )
    (net (code "89") (name "KEY_POS12") (class "Default")
      (node (ref "1") (pin "22") (pinfunction "22_22") (pintype "passive"))
      (node (ref "U1") (pin "2") (pinfunction "PC13_2") (pintype "passive"))
    )
    (net (code "90") (name "KEY_POS13") (class "Default")
      (node (ref "1") (pin "23") (pinfunction "23_23") (pintype "passive"))
      (node (ref "U1") (pin "3") (pinfunction "OSC32_IN/PC14_3") (pintype "passive"))
    )
    (net (code "91") (name "KEY_POS14") (class "Default")
      (node (ref "1") (pin "24") (pinfunction "24_24") (pintype "passive"))
      (node (ref "U1") (pin "4") (pinfunction "OSC32_OUT/PC15_4") (pintype "passive"))
    )
    (net (code "92") (name "KEY_SEG1") (class "Default")
      (node (ref "1") (pin "31") (pinfunction "31_31") (pintype "passive"))
      (node (ref "U1") (pin "27") (pinfunction "PB1_27") (pintype "passive"))
    )
    (net (code "93") (name "KEY_SEG2") (class "Default")
      (node (ref "1") (pin "30") (pinfunction "30_30") (pintype "passive"))
      (node (ref "U1") (pin "29") (pinfunction "PB10_29") (pintype "passive"))
    )
    (net (code "94") (name "KEY_SEG3") (class "Default")
      (node (ref "1") (pin "29") (pinfunction "29_29") (pintype "passive"))
      (node (ref "U1") (pin "30") (pinfunction "PB11_30") (pintype "passive"))
    )
    (net (code "95") (name "KEY_SEG4") (class "Default")
      (node (ref "1") (pin "28") (pinfunction "28_28") (pintype "passive"))
      (node (ref "U1") (pin "33") (pinfunction "PB12_33") (pintype "passive"))
    )
    (net (code "96") (name "KEY_SEG5") (class "Default")
      (node (ref "1") (pin "27") (pinfunction "27_27") (pintype "passive"))
      (node (ref "U1") (pin "34") (pinfunction "PB13_34") (pintype "passive"))
    )
    (net (code "97") (name "KEY_SEG6") (class "Default")
      (node (ref "1") (pin "26") (pinfunction "26_26") (pintype "passive"))
      (node (ref "U1") (pin "35") (pinfunction "PB14_35") (pintype "passive"))
    )
    (net (code "98") (name "Net-(1-Pad35)") (class "Default")
      (node (ref "1") (pin "35") (pinfunction "35_35") (pintype "passive"))
      (node (ref "R1") (pin "5") (pinfunction "5_5") (pintype "passive"))
    )
    (net (code "99") (name "Net-(1-Pad36)") (class "Default")
      (node (ref "1") (pin "36") (pinfunction "36_36") (pintype "passive"))
      (node (ref "R1") (pin "6") (pinfunction "6_6") (pintype "passive"))
    )
    (net (code "100") (name "Net-(1-Pad37)") (class "Default")
      (node (ref "1") (pin "37") (pinfunction "37_37") (pintype "passive"))
      (node (ref "R1") (pin "7") (pinfunction "7_7") (pintype "passive"))
    )
    (net (code "101") (name "Net-(1-Pad38)") (class "Default")
      (node (ref "1") (pin "38") (pinfunction "38_38") (pintype "passive"))
      (node (ref "R1") (pin "8") (pinfunction "8_8") (pintype "passive"))
    )
    (net (code "102") (name "Net-(D6-K)") (class "Default")
      (node (ref "D6") (pin "1") (pinfunction "K_1") (pintype "passive"))
      (node (ref "D7") (pin "1") (pinfunction "K_1") (pintype "passive"))
      (node (ref "R25") (pin "1") (pinfunction "1_1") (pintype "passive"))
    )
    (net (code "103") (name "Net-(F1-Pad2)") (class "Default")
      (node (ref "F1") (pin "2") (pinfunction "2_2") (pintype "passive"))
      (node (ref "P1") (pin "4") (pinfunction "4_4") (pintype "passive"))
    )
    (net (code "104") (name "Net-(IC2-SENSE)") (class "Default")
      (node (ref "IC2") (pin "4") (pinfunction "SENSE_4") (pintype "passive"))
      (node (ref "R27") (pin "1") (pinfunction "1_1") (pintype "passive"))
    )
    (net (code "105") (name "Net-(IC2-~{SD})") (class "Default")
      (node (ref "IC2") (pin "1") (pinfunction "~{SD}_1") (pintype "passive"))
      (node (ref "R24") (pin "2") (pinfunction "2_2") (pintype "passive"))
      (node (ref "R26") (pin "2") (pinfunction "2_2") (pintype "passive"))
    )
    (net (code "106") (name "Net-(P1-Pad1)") (class "Default")
      (node (ref "P1") (pin "1") (pinfunction "1_1") (pintype "passive"))
      (node (ref "R2") (pin "2") (pinfunction "2_2") (pintype "passive"))
    )
    (net (code "107") (name "Net-(P1-Pad2)") (class "Default")
      (node (ref "P1") (pin "2") (pinfunction "2_2") (pintype "passive"))
      (node (ref "R3") (pin "2") (pinfunction "2_2") (pintype "passive"))
    )
    (net (code "108") (name "Net-(P3-Pad2)") (class "Default")
      (node (ref "P3") (pin "2") (pinfunction "2_2") (pintype "passive"))
      (node (ref "R19") (pin "1") (pinfunction "1_1") (pintype "passive"))
    )
    (net (code "109") (name "Net-(P3-Pad3)") (class "Default")
      (node (ref "P3") (pin "3") (pinfunction "3_3") (pintype "passive"))
      (node (ref "R19") (pin "2") (pinfunction "2_2") (pintype "passive"))
    )
    (net (code "110") (name "Net-(P3-Pad4)") (class "Default")
      (node (ref "P3") (pin "4") (pinfunction "4_4") (pintype "passive"))
      (node (ref "R19") (pin "3") (pinfunction "3_3") (pintype "passive"))
    )
    (net (code "111") (name "Net-(P3-Pad5)") (class "Default")
      (node (ref "P3") (pin "5") (pinfunction "5_5") (pintype "passive"))
      (node (ref "R19") (pin "4") (pinfunction "4_4") (pintype "passive"))
    )
    (net (code "112") (name "Net-(Q1-B)") (class "Default")
      (node (ref "Q1") (pin "1") (pinfunction "B_1") (pintype "passive"))
      (node (ref "R4") (pin "2") (pinfunction "2_2") (pintype "passive"))
      (node (ref "R6") (pin "1") (pinfunction "1_1") (pintype "passive"))
    )
    (net (code "113") (name "Net-(Q1-C)") (class "Default")
      (node (ref "Q1") (pin "3") (pinfunction "C_3") (pintype "passive"))
      (node (ref "R7") (pin "2") (pinfunction "2_2") (pintype "passive"))
    )
    (net (code "114") (name "Net-(R13-Pad2)") (class "Default")
      (node (ref "R13") (pin "2") (pinfunction "2_2") (pintype "passive"))
      (node (ref "R14") (pin "1") (pinfunction "1_1") (pintype "passive"))
      (node (ref "U7") (pin "3") (pinfunction "EN_3") (pintype "passive"))
    )
    (net (code "115") (name "Net-(U1-RCC_OSC_IN{slash}PH0)") (class "Default")
      (node (ref "C1") (pin "1") (pinfunction "1_1") (pintype "passive"))
      (node (ref "U1") (pin "5") (pinfunction "RCC_OSC_IN/PH0_5") (pintype "passive"))
      (node (ref "X1") (pin "3") (pinfunction "3_3") (pintype "passive"))
    )
    (net (code "116") (name "Net-(U1-RCC_OSC_OUT{slash}PH1)") (class "Default")
      (node (ref "C2") (pin "1") (pinfunction "1_1") (pintype "passive"))
      (node (ref "U1") (pin "6") (pinfunction "RCC_OSC_OUT/PH1_6") (pintype "passive"))
      (node (ref "X1") (pin "1") (pinfunction "1_1") (pintype "passive"))
    )
    (net (code "117") (name "Net-(U1-VCAP_1)") (class "Default")
      (node (ref "C17") (pin "2") (pinfunction "2_2") (pintype "passive"))
      (node (ref "U1") (pin "31") (pinfunction "VCAP_1_31") (pintype "passive"))
    )
    (net (code "118") (name "Net-(U1-VCAP_2)") (class "Default")
      (node (ref "C18") (pin "2") (pinfunction "2_2") (pintype "passive"))
      (node (ref "U1") (pin "47") (pinfunction "VCAP_2_47") (pintype "passive"))
    )
    (net (code "119") (name "Net-(U9-VDD)") (class "Default")
      (node (ref "C54") (pin "2") (pinfunction "2_2") (pintype "passive"))
      (node (ref "R31") (pin "2") (pinfunction "2_2") (pintype "passive"))
      (node (ref "U9") (pin "6") (pinfunction "VDD_6") (pintype "passive"))
    )
    (net (code "120") (name "USBVCC") (class "Default")
      (node (ref "C28") (pin "2") (pinfunction "2_2") (pintype "passive"))
      (node (ref "U4") (pin "1") (pinfunction "S1_1") (pintype "passive"))
      (node (ref "U4") (pin "3") (pinfunction "S2_3") (pintype "passive"))
      (node (ref "U5") (pin "12") (pinfunction "VBUS_C_12") (pintype "passive"))
      (node (ref "USB1") (pin "A4") (pinfunction "VBUS_A4") (pintype "passive"))
      (node (ref "USB1") (pin "A9") (pinfunction "VBUS_A9") (pintype "passive"))
      (node (ref "USB1") (pin "B4") (pinfunction "VBUS_B4") (pintype "passive"))
      (node (ref "USB1") (pin "B9") (pinfunction "VBUS_B9") (pintype "passive"))
    )
    (net (code "121") (name "VCC") (class "Default")
      (node (ref "D6") (pin "2") (pinfunction "A_2") (pintype "passive"))
      (node (ref "R20") (pin "2") (pinfunction "2_2") (pintype "passive"))
      (node (ref "R21") (pin "2") (pinfunction "2_2") (pintype "passive"))
      (node (ref "U5") (pin "19") (pinfunction "VCC_19") (pintype "passive"))
    )
    (net (code "122") (name "VCC3V3") (class "Default")
      (node (ref "C11") (pin "2") (pinfunction "2_2") (pintype "passive"))
      (node (ref "C12") (pin "2") (pinfunction "2_2") (pintype "passive"))
      (node (ref "C24") (pin "1") (pinfunction "1_1") (pintype "passive"))
      (node (ref "C25") (pin "1") (pinfunction "1_1") (pintype "passive"))
      (node (ref "C4") (pin "2") (pinfunction "2_2") (pintype "passive"))
      (node (ref "C5") (pin "2") (pinfunction "2_2") (pintype "passive"))
      (node (ref "C6") (pin "2") (pinfunction "2_2") (pintype "passive"))
      (node (ref "C7") (pin "2") (pinfunction "2_2") (pintype "passive"))
      (node (ref "F1") (pin "1") (pinfunction "1_1") (pintype "passive"))
      (node (ref "R11") (pin "1") (pinfunction "1_1") (pintype "passive"))
      (node (ref "R15") (pin "1") (pinfunction "1_1") (pintype "passive"))
      (node (ref "R16") (pin "1") (pinfunction "1_1") (pintype "passive"))
      (node (ref "R17") (pin "1") (pinfunction "1_1") (pintype "passive"))
      (node (ref "R8") (pin "2") (pinfunction "2_2") (pintype "passive"))
      (node (ref "U1") (pin "1") (pinfunction "VBAT_1") (pintype "passive"))
      (node (ref "U1") (pin "19") (pinfunction "VDD_19") (pintype "passive"))
      (node (ref "U1") (pin "32") (pinfunction "VDD_32") (pintype "passive"))
      (node (ref "U1") (pin "48") (pinfunction "VDD_48") (pintype "passive"))
      (node (ref "U1") (pin "64") (pinfunction "VDD_64") (pintype "passive"))
      (node (ref "U3") (pin "5") (pinfunction "VOUT_5") (pintype "passive"))
    )
    (net (code "123") (name "VCC3V3_1A") (class "Default")
      (node (ref "1") (pin "33") (pinfunction "33_33") (pintype "passive"))
      (node (ref "C52") (pin "1") (pinfunction "1_1") (pintype "passive"))
      (node (ref "C53") (pin "1") (pinfunction "1_1") (pintype "passive"))
      (node (ref "IC2") (pin "3") (pinfunction "OUT_3") (pintype "output"))
      (node (ref "R27") (pin "2") (pinfunction "2_2") (pintype "passive"))
    )
    (net (code "124") (name "VCC_BLE") (class "Default")
      (node (ref "C15") (pin "1") (pinfunction "1_1") (pintype "passive"))
      (node (ref "C16") (pin "1") (pinfunction "1_1") (pintype "passive"))
      (node (ref "C47") (pin "2") (pinfunction "2_2") (pintype "passive"))
      (node (ref "C48") (pin "2") (pinfunction "2_2") (pintype "passive"))
      (node (ref "IC1") (pin "2") (pinfunction "3V3_2") (pintype "passive"))
      (node (ref "P3") (pin "1") (pinfunction "1_1") (pintype "passive"))
      (node (ref "R18") (pin "2") (pinfunction "2_2") (pintype "passive"))
      (node (ref "U2") (pin "5") (pinfunction "VOUT_5") (pintype "passive"))
    )
    (net (code "125") (name "VCC_BUS") (class "Default")
      (node (ref "C13") (pin "1") (pinfunction "1_1") (pintype "passive"))
      (node (ref "C14") (pin "1") (pinfunction "1_1") (pintype "passive"))
      (node (ref "C22") (pin "1") (pinfunction "1_1") (pintype "passive"))
      (node (ref "C23") (pin "1") (pinfunction "1_1") (pintype "passive"))
      (node (ref "C42") (pin "1") (pinfunction "1_1") (pintype "passive"))
      (node (ref "C43") (pin "1") (pinfunction "1_1") (pintype "passive"))
      (node (ref "C50") (pin "1") (pinfunction "1_1") (pintype "passive"))
      (node (ref "C51") (pin "1") (pinfunction "1_1") (pintype "passive"))
      (node (ref "IC2") (pin "2") (pinfunction "IN_2") (pintype "input"))
      (node (ref "R25") (pin "2") (pinfunction "2_2") (pintype "passive"))
      (node (ref "U2") (pin "1") (pinfunction "EN_1") (pintype "passive"))
      (node (ref "U3") (pin "1") (pinfunction "EN_1") (pintype "passive"))
      (node (ref "U3") (pin "3") (pinfunction "EN_3") (pintype "passive"))
      (node (ref "U7") (pin "1") (pinfunction "EN_1") (pintype "passive"))
    )
    (net (code "126") (name "VCC_LCD") (class "Default")
      (node (ref "1") (pin "39") (pinfunction "39_39") (pintype "passive"))
      (node (ref "C44") (pin "1") (pinfunction "1_1") (pintype "passive"))
      (node (ref "C45") (pin "1") (pinfunction "1_1") (pintype "passive"))
      (node (ref "P2") (pin "4") (pinfunction "4_4") (pintype "passive"))
      (node (ref "P2") (pin "6") (pinfunction "6_6") (pintype "passive"))
      (node (ref "Q1") (pin "2") (pinfunction "E_2") (pintype "passive"))
      (node (ref "R6") (pin "2") (pinfunction "2_2") (pintype "passive"))
      (node (ref "U7") (pin "5") (pinfunction "VOUT_5") (pintype "passive"))
    )
    (net (code "127") (name "unconnected-(IC1-IO1-Pad39)") (class "Default")
      (node (ref "IC1") (pin "39") (pinfunction "IO1_39") (pintype "passive+no_connect"))
    )
    (net (code "128") (name "unconnected-(IC1-IO2-Pad38)") (class "Default")
      (node (ref "IC1") (pin "38") (pinfunction "IO2_38") (pintype "passive+no_connect"))
    )
    (net (code "129") (name "unconnected-(IC1-IO3-Pad15)") (class "Default")
      (node (ref "IC1") (pin "15") (pinfunction "IO3_15") (pintype "passive+no_connect"))
    )
    (net (code "130") (name "unconnected-(IC1-IO4-Pad4)") (class "Default")
      (node (ref "IC1") (pin "4") (pinfunction "IO4_4") (pintype "passive+no_connect"))
    )
    (net (code "131") (name "unconnected-(IC1-IO5-Pad5)") (class "Default")
      (node (ref "IC1") (pin "5") (pinfunction "IO5_5") (pintype "passive+no_connect"))
    )
    (net (code "132") (name "unconnected-(IC1-IO6-Pad6)") (class "Default")
      (node (ref "IC1") (pin "6") (pinfunction "IO6_6") (pintype "passive+no_connect"))
    )
    (net (code "133") (name "unconnected-(IC1-IO7-Pad7)") (class "Default")
      (node (ref "IC1") (pin "7") (pinfunction "IO7_7") (pintype "passive+no_connect"))
    )
    (net (code "134") (name "unconnected-(IC1-IO8-Pad12)") (class "Default")
      (node (ref "IC1") (pin "12") (pinfunction "IO8_12") (pintype "passive+no_connect"))
    )
    (net (code "135") (name "unconnected-(IC1-IO9-Pad17)") (class "Default")
      (node (ref "IC1") (pin "17") (pinfunction "IO9_17") (pintype "passive+no_connect"))
    )
    (net (code "136") (name "unconnected-(IC1-IO10-Pad18)") (class "Default")
      (node (ref "IC1") (pin "18") (pinfunction "IO10_18") (pintype "passive+no_connect"))
    )
    (net (code "137") (name "unconnected-(IC1-IO11-Pad19)") (class "Default")
      (node (ref "IC1") (pin "19") (pinfunction "IO11_19") (pintype "passive+no_connect"))
    )
    (net (code "138") (name "unconnected-(IC1-IO12-Pad20)") (class "Default")
      (node (ref "IC1") (pin "20") (pinfunction "IO12_20") (pintype "passive+no_connect"))
    )
    (net (code "139") (name "unconnected-(IC1-IO13-Pad21)") (class "Default")
      (node (ref "IC1") (pin "21") (pinfunction "IO13_21") (pintype "passive+no_connect"))
    )
    (net (code "140") (name "unconnected-(IC1-IO14-Pad22)") (class "Default")
      (node (ref "IC1") (pin "22") (pinfunction "IO14_22") (pintype "passive+no_connect"))
    )
    (net (code "141") (name "unconnected-(IC1-IO15-Pad8)") (class "Default")
      (node (ref "IC1") (pin "8") (pinfunction "IO15_8") (pintype "passive+no_connect"))
    )
    (net (code "142") (name "unconnected-(IC1-IO16-Pad9)") (class "Default")
      (node (ref "IC1") (pin "9") (pinfunction "IO16_9") (pintype "passive+no_connect"))
    )
    (net (code "143") (name "unconnected-(IC1-IO19-Pad13)") (class "Default")
      (node (ref "IC1") (pin "13") (pinfunction "IO19_13") (pintype "passive+no_connect"))
    )
    (net (code "144") (name "unconnected-(IC1-IO20-Pad14)") (class "Default")
      (node (ref "IC1") (pin "14") (pinfunction "IO20_14") (pintype "passive+no_connect"))
    )
    (net (code "145") (name "unconnected-(IC1-IO21-Pad23)") (class "Default")
      (node (ref "IC1") (pin "23") (pinfunction "IO21_23") (pintype "passive+no_connect"))
    )
    (net (code "146") (name "unconnected-(IC1-IO35-Pad28)") (class "Default")
      (node (ref "IC1") (pin "28") (pinfunction "IO35_28") (pintype "passive+no_connect"))
    )
    (net (code "147") (name "unconnected-(IC1-IO36-Pad29)") (class "Default")
      (node (ref "IC1") (pin "29") (pinfunction "IO36_29") (pintype "passive+no_connect"))
    )
    (net (code "148") (name "unconnected-(IC1-IO37-Pad30)") (class "Default")
      (node (ref "IC1") (pin "30") (pinfunction "IO37_30") (pintype "passive+no_connect"))
    )
    (net (code "149") (name "unconnected-(IC1-IO38-Pad31)") (class "Default")
      (node (ref "IC1") (pin "31") (pinfunction "IO38_31") (pintype "passive+no_connect"))
    )
    (net (code "150") (name "unconnected-(IC1-IO39-Pad32)") (class "Default")
      (node (ref "IC1") (pin "32") (pinfunction "IO39_32") (pintype "passive+no_connect"))
    )
    (net (code "151") (name "unconnected-(IC1-IO40-Pad33)") (class "Default")
      (node (ref "IC1") (pin "33") (pinfunction "IO40_33") (pintype "passive+no_connect"))
    )
    (net (code "152") (name "unconnected-(IC1-IO41-Pad34)") (class "Default")
      (node (ref "IC1") (pin "34") (pinfunction "IO41_34") (pintype "passive+no_connect"))
    )
    (net (code "153") (name "unconnected-(IC1-IO42-Pad35)") (class "Default")
      (node (ref "IC1") (pin "35") (pinfunction "IO42_35") (pintype "passive+no_connect"))
    )
    (net (code "154") (name "unconnected-(IC1-IO45-Pad26)") (class "Default")
      (node (ref "IC1") (pin "26") (pinfunction "IO45_26") (pintype "passive+no_connect"))
    )
    (net (code "155") (name "unconnected-(IC1-IO46-Pad16)") (class "Default")
      (node (ref "IC1") (pin "16") (pinfunction "IO46_16") (pintype "passive+no_connect"))
    )
    (net (code "156") (name "unconnected-(IC1-IO47-Pad24)") (class "Default")
      (node (ref "IC1") (pin "24") (pinfunction "IO47_24") (pintype "passive+no_connect"))
    )
    (net (code "157") (name "unconnected-(IC1-IO48-Pad25)") (class "Default")
      (node (ref "IC1") (pin "25") (pinfunction "IO48_25") (pintype "passive+no_connect"))
    )
    (net (code "158") (name "unconnected-(P1-PadMP1)") (class "Default")
      (node (ref "P1") (pin "MP1") (pinfunction "MP1_MP1") (pintype "passive+no_connect"))
    )
    (net (code "159") (name "unconnected-(P1-PadMP2)") (class "Default")
      (node (ref "P1") (pin "MP2") (pinfunction "MP2_MP2") (pintype "passive+no_connect"))
    )
    (net (code "160") (name "unconnected-(P2-PadMP1)") (class "Default")
      (node (ref "P2") (pin "MP1") (pinfunction "MP1_MP1") (pintype "passive+no_connect"))
    )
    (net (code "161") (name "unconnected-(P2-PadMP2)") (class "Default")
      (node (ref "P2") (pin "MP2") (pinfunction "MP2_MP2") (pintype "passive+no_connect"))
    )
    (net (code "162") (name "unconnected-(P3-PadMP1)") (class "Default")
      (node (ref "P3") (pin "MP1") (pinfunction "MP1_MP1") (pintype "passive+no_connect"))
    )
    (net (code "163") (name "unconnected-(P3-PadMP2)") (class "Default")
      (node (ref "P3") (pin "MP2") (pinfunction "MP2_MP2") (pintype "passive+no_connect"))
    )
    (net (code "164") (name "unconnected-(P4-PadMP1)") (class "Default")
      (node (ref "P4") (pin "MP1") (pinfunction "MP1_MP1") (pintype "passive+no_connect"))
    )
    (net (code "165") (name "unconnected-(P4-PadMP2)") (class "Default")
      (node (ref "P4") (pin "MP2") (pinfunction "MP2_MP2") (pintype "passive+no_connect"))
    )
    (net (code "166") (name "unconnected-(R32-Pad2)") (class "Default")
      (node (ref "R32") (pin "2") (pinfunction "2_2") (pintype "passive+no_connect"))
    )
    (net (code "167") (name "unconnected-(R33-Pad2)") (class "Default")
      (node (ref "R33") (pin "2") (pinfunction "2_2") (pintype "passive+no_connect"))
    )
    (net (code "168") (name "unconnected-(U2-NC-Pad4)") (class "Default")
      (node (ref "U2") (pin "4") (pinfunction "NC_4") (pintype "passive+no_connect"))
    )
    (net (code "169") (name "unconnected-(U3-NC-Pad4)") (class "Default")
      (node (ref "U3") (pin "4") (pinfunction "NC_4") (pintype "passive+no_connect"))
    )
    (net (code "170") (name "unconnected-(U7-NC-Pad4)") (class "Default")
      (node (ref "U7") (pin "4") (pinfunction "NC_4") (pintype "passive+no_connect"))
    )
    (net (code "171") (name "unconnected-(USB1-RX1+-PadB11)") (class "Default")
      (node (ref "USB1") (pin "B11") (pinfunction "RX1+_B11") (pintype "passive+no_connect"))
    )
    (net (code "172") (name "unconnected-(USB1-RX1--PadB10)") (class "Default")
      (node (ref "USB1") (pin "B10") (pinfunction "RX1-_B10") (pintype "passive+no_connect"))
    )
    (net (code "173") (name "unconnected-(USB1-RX2+-PadA11)") (class "Default")
      (node (ref "USB1") (pin "A11") (pinfunction "RX2+_A11") (pintype "passive+no_connect"))
    )
    (net (code "174") (name "unconnected-(USB1-RX2--PadA10)") (class "Default")
      (node (ref "USB1") (pin "A10") (pinfunction "RX2-_A10") (pintype "passive+no_connect"))
    )
    (net (code "175") (name "unconnected-(USB1-SBU1-PadA8)") (class "Default")
      (node (ref "USB1") (pin "A8") (pinfunction "SBU1_A8") (pintype "passive+no_connect"))
    )
    (net (code "176") (name "unconnected-(USB1-SBU2-PadB8)") (class "Default")
      (node (ref "USB1") (pin "B8") (pinfunction "SBU2_B8") (pintype "passive+no_connect"))
    )
    (net (code "177") (name "unconnected-(USB1-SH1-Pad1)") (class "Default")
      (node (ref "USB1") (pin "1") (pinfunction "SH1_1") (pintype "passive+no_connect"))
    )
    (net (code "178") (name "unconnected-(USB1-SH2-Pad2)") (class "Default")
      (node (ref "USB1") (pin "2") (pinfunction "SH2_2") (pintype "passive+no_connect"))
    )
    (net (code "179") (name "unconnected-(USB1-SH3-Pad3)") (class "Default")
      (node (ref "USB1") (pin "3") (pinfunction "SH3_3") (pintype "passive+no_connect"))
    )
    (net (code "180") (name "unconnected-(USB1-SH4-Pad4)") (class "Default")
      (node (ref "USB1") (pin "4") (pinfunction "SH4_4") (pintype "passive+no_connect"))
    )
    (net (code "181") (name "unconnected-(USB1-TX1+-PadA2)") (class "Default")
      (node (ref "USB1") (pin "A2") (pinfunction "TX1+_A2") (pintype "passive+no_connect"))
    )
    (net (code "182") (name "unconnected-(USB1-TX1--PadA3)") (class "Default")
      (node (ref "USB1") (pin "A3") (pinfunction "TX1-_A3") (pintype "passive+no_connect"))
    )
    (net (code "183") (name "unconnected-(USB1-TX2+-PadB2)") (class "Default")
      (node (ref "USB1") (pin "B2") (pinfunction "TX2+_B2") (pintype "passive+no_connect"))
    )
    (net (code "184") (name "unconnected-(USB1-TX2--PadB3)") (class "Default")
      (node (ref "USB1") (pin "B3") (pinfunction "TX2-_B3") (pintype "passive+no_connect"))
    )
  )
)
